# CntrlBoardV2_0.net
KiCad netlist of a schematic drawn in EAGLE
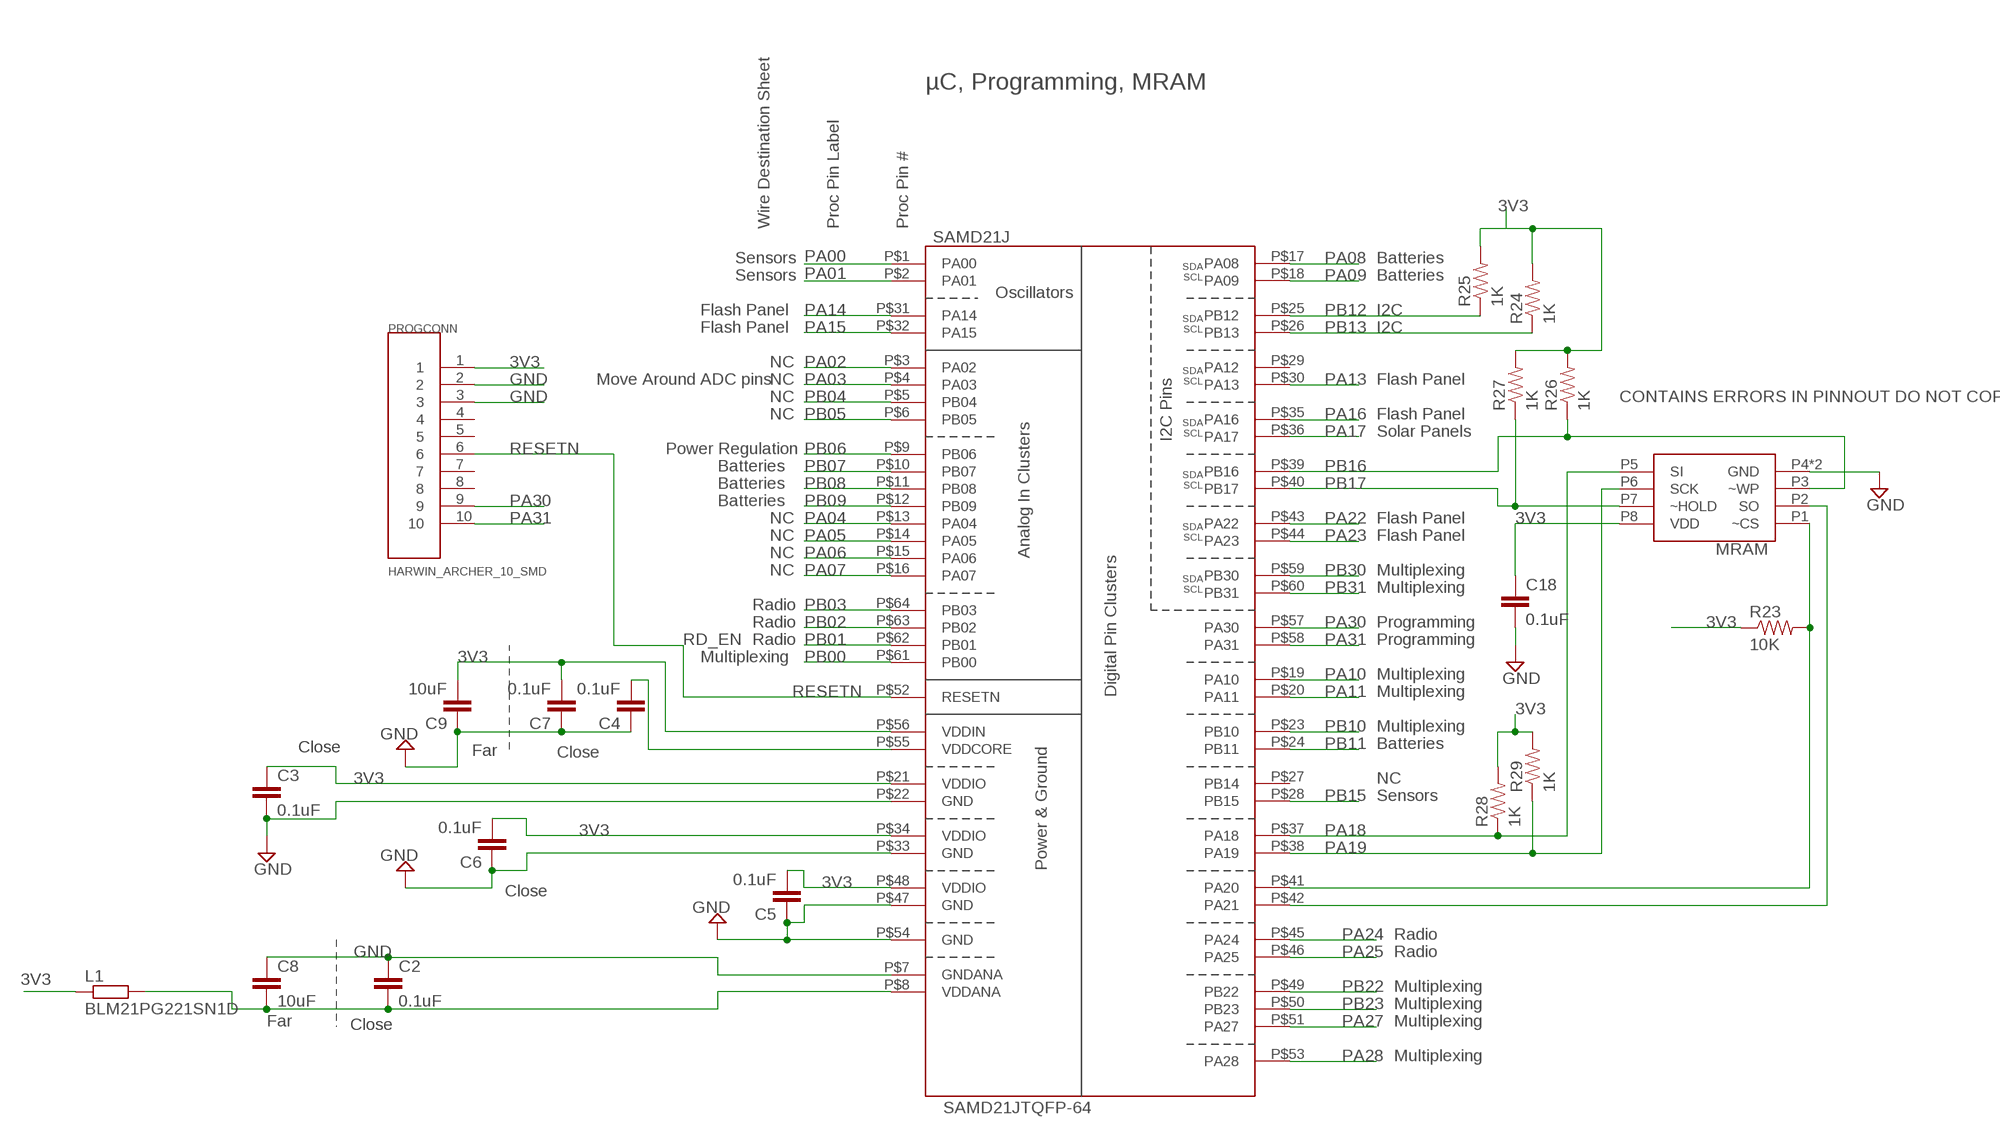
[diagram p0: schematic, sheet 1]
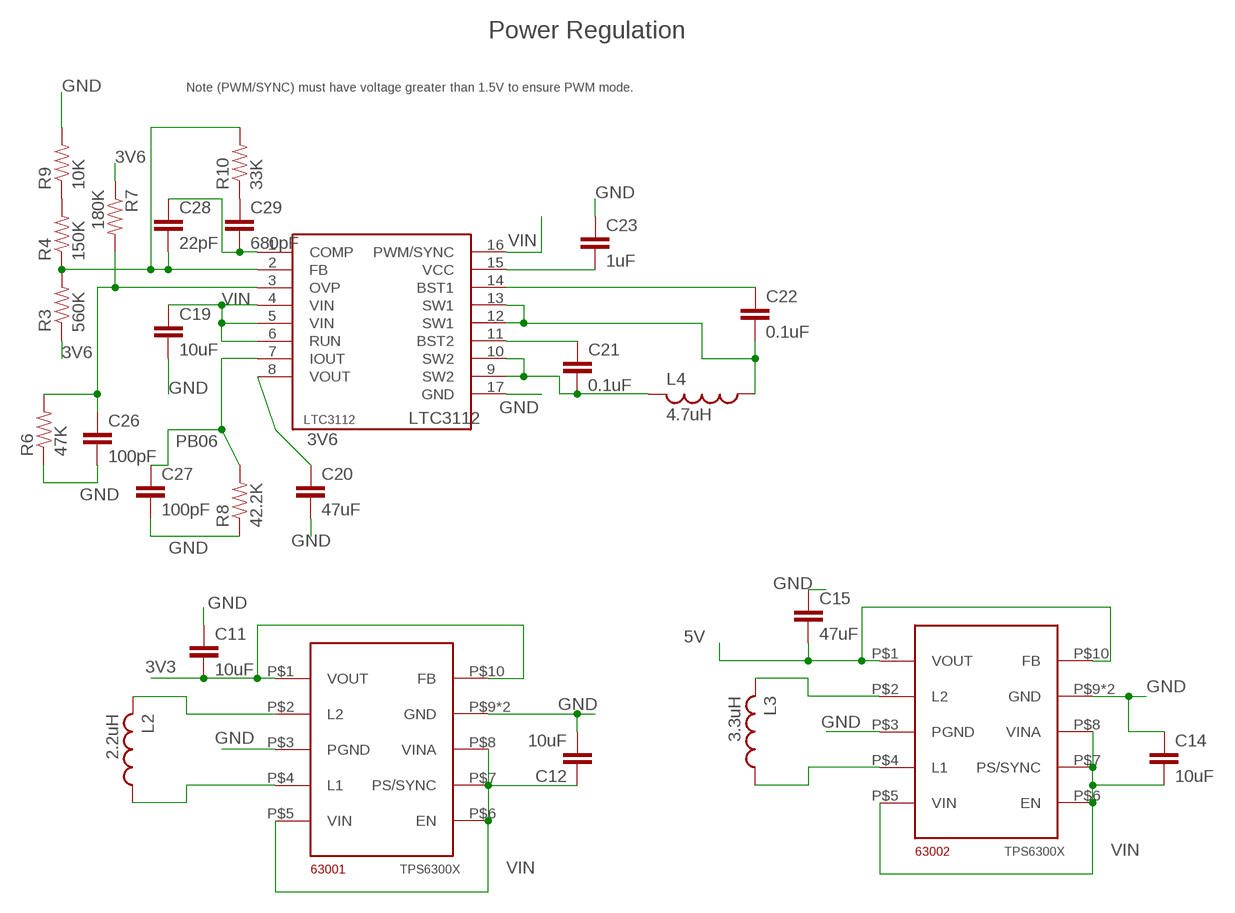
[diagram p1: schematic, sheet 2]
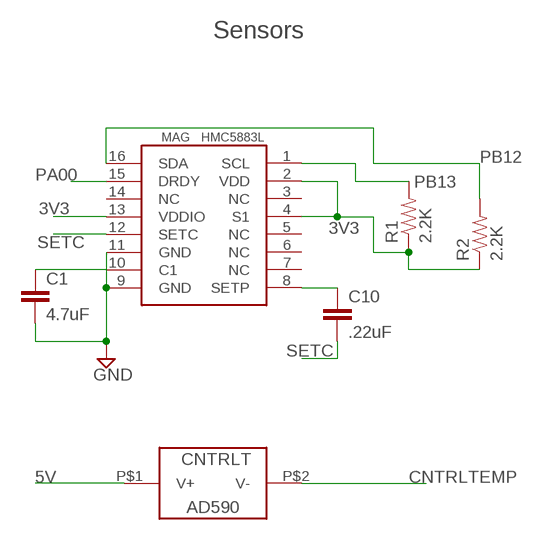
[diagram p2: schematic, sheet 3]
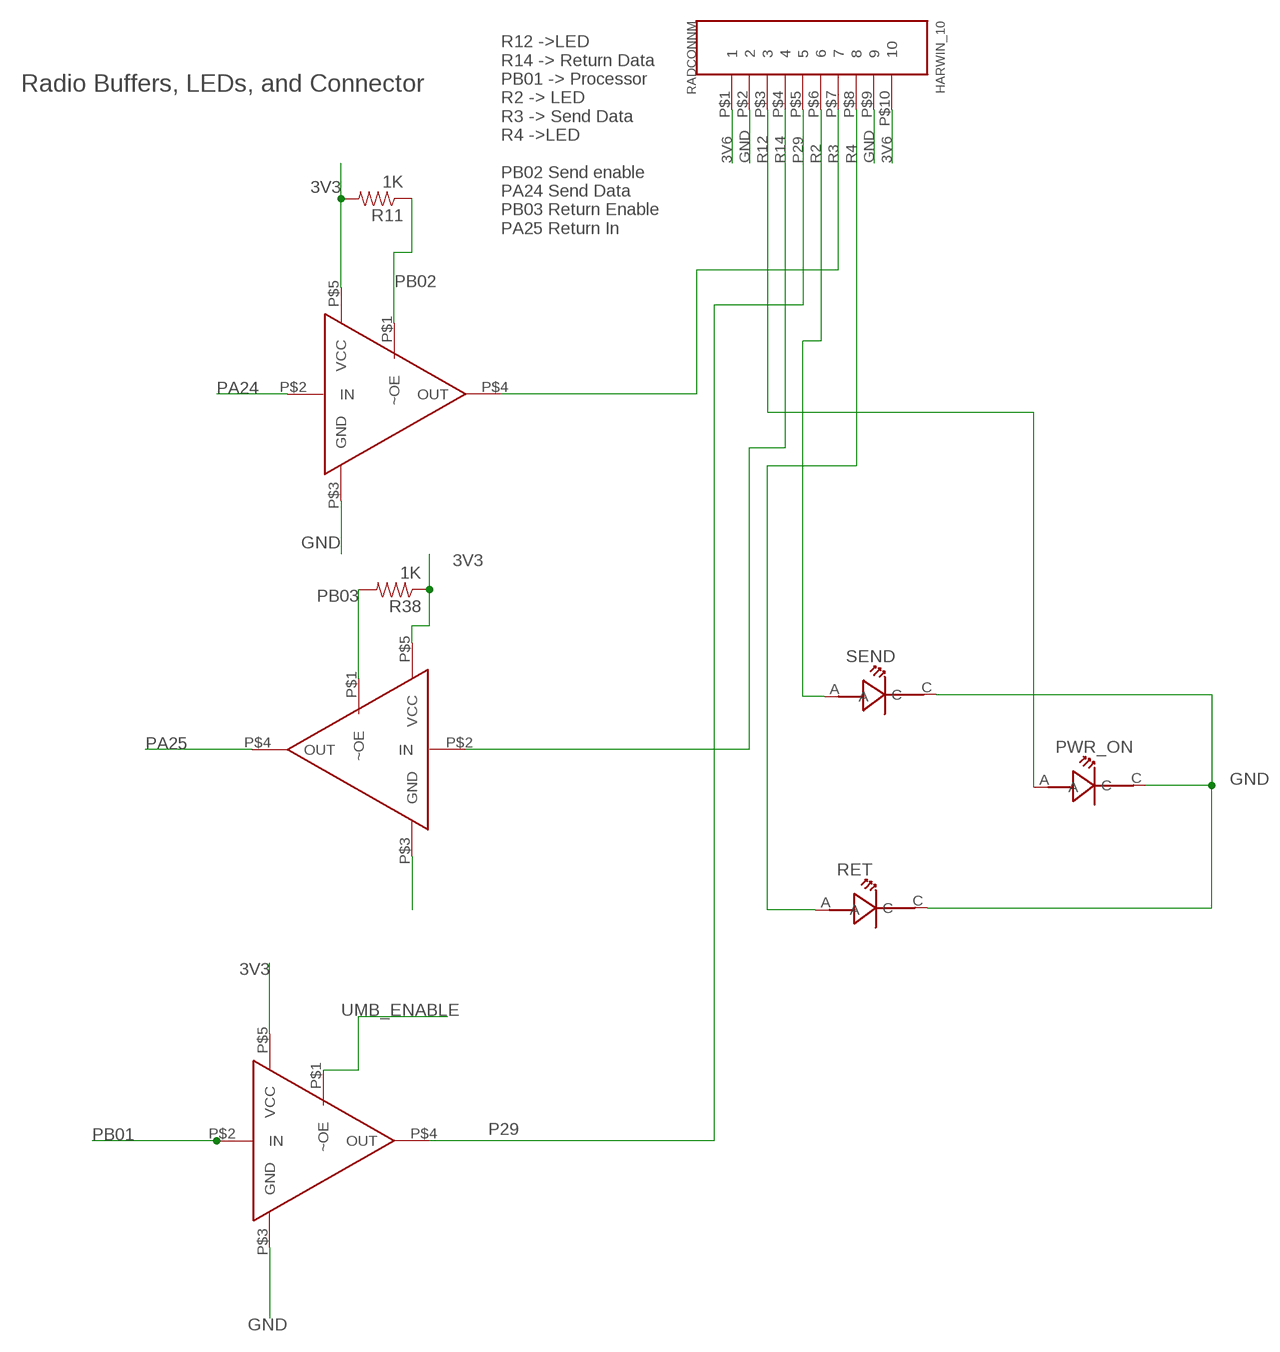
[diagram p3: schematic, sheet 4]
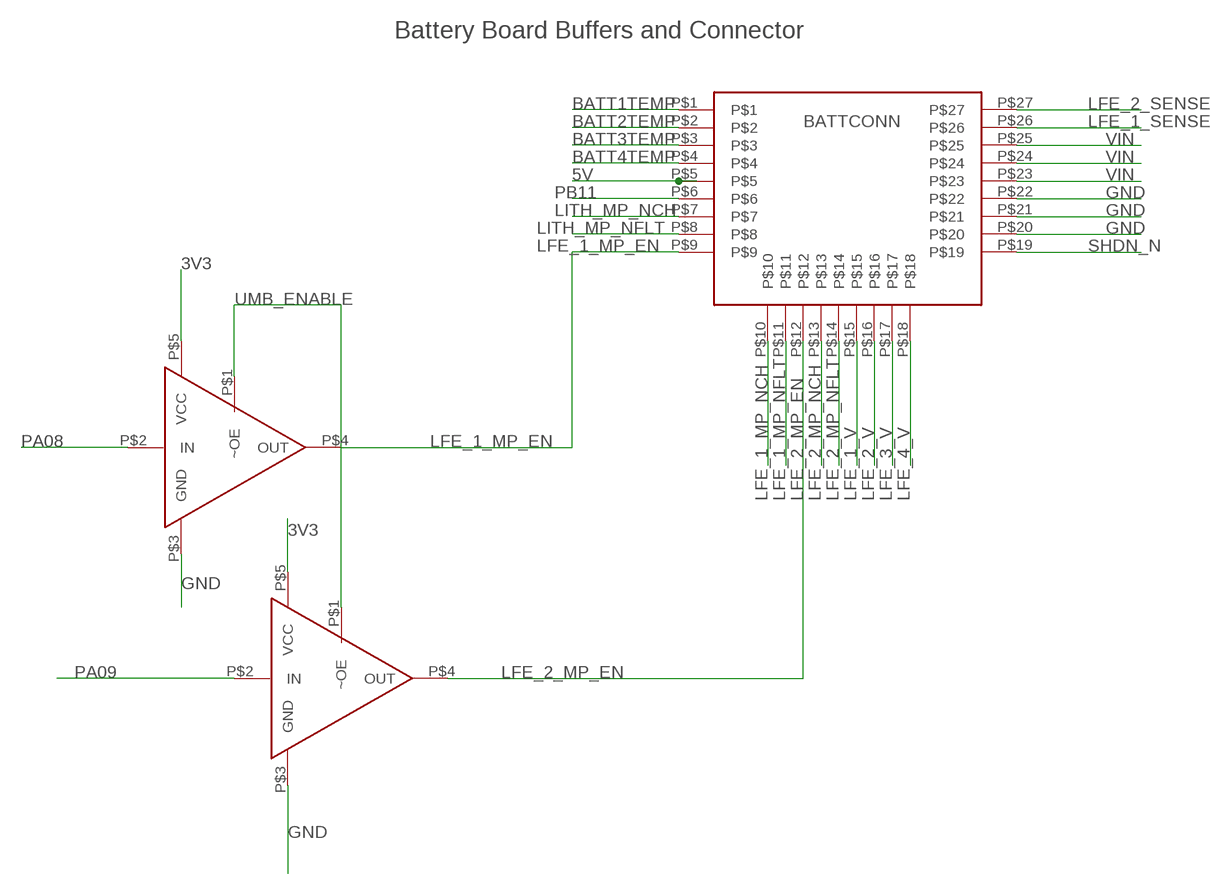
[diagram p4: schematic, sheet 5]
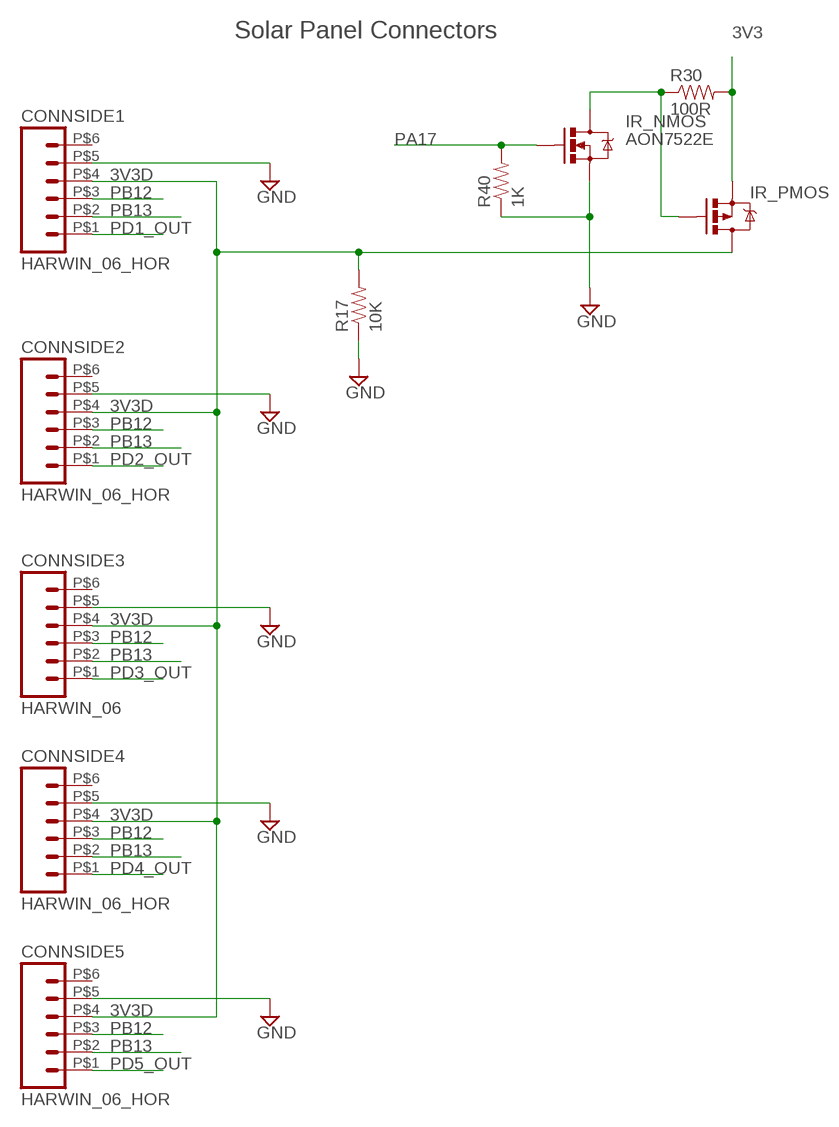
[diagram p5: schematic, sheet 6]
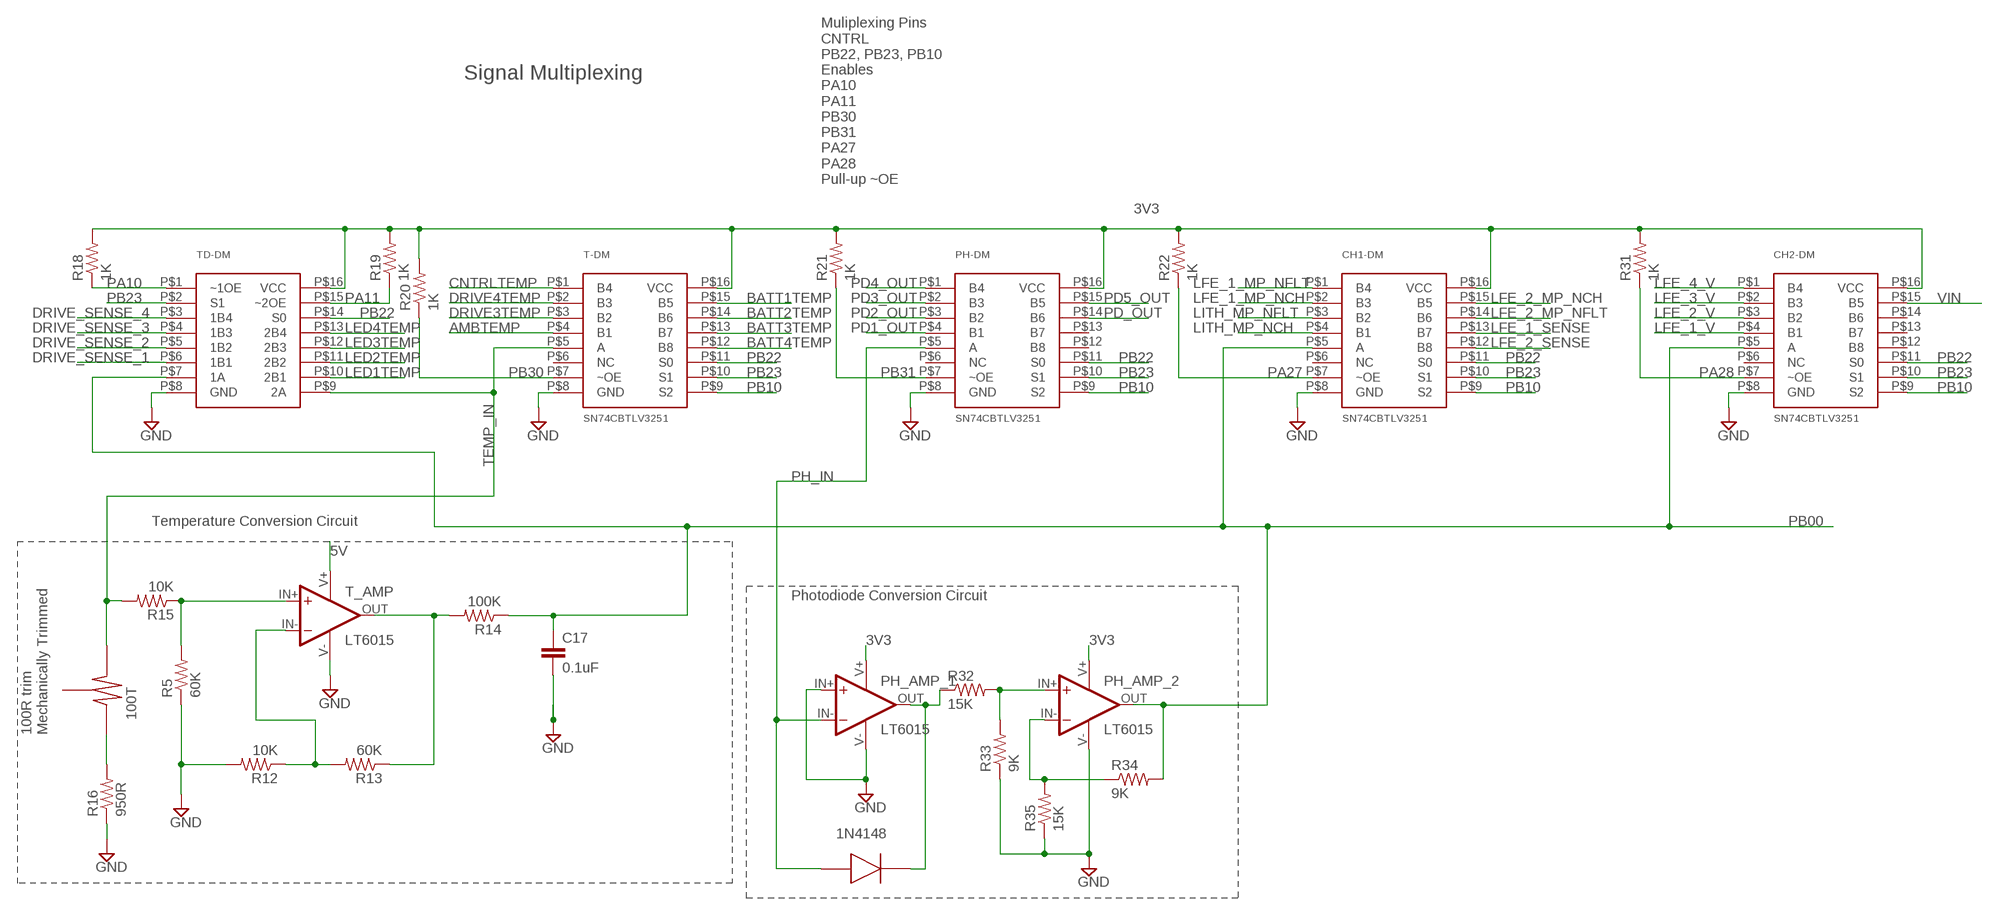
[diagram p6: schematic, sheet 7]
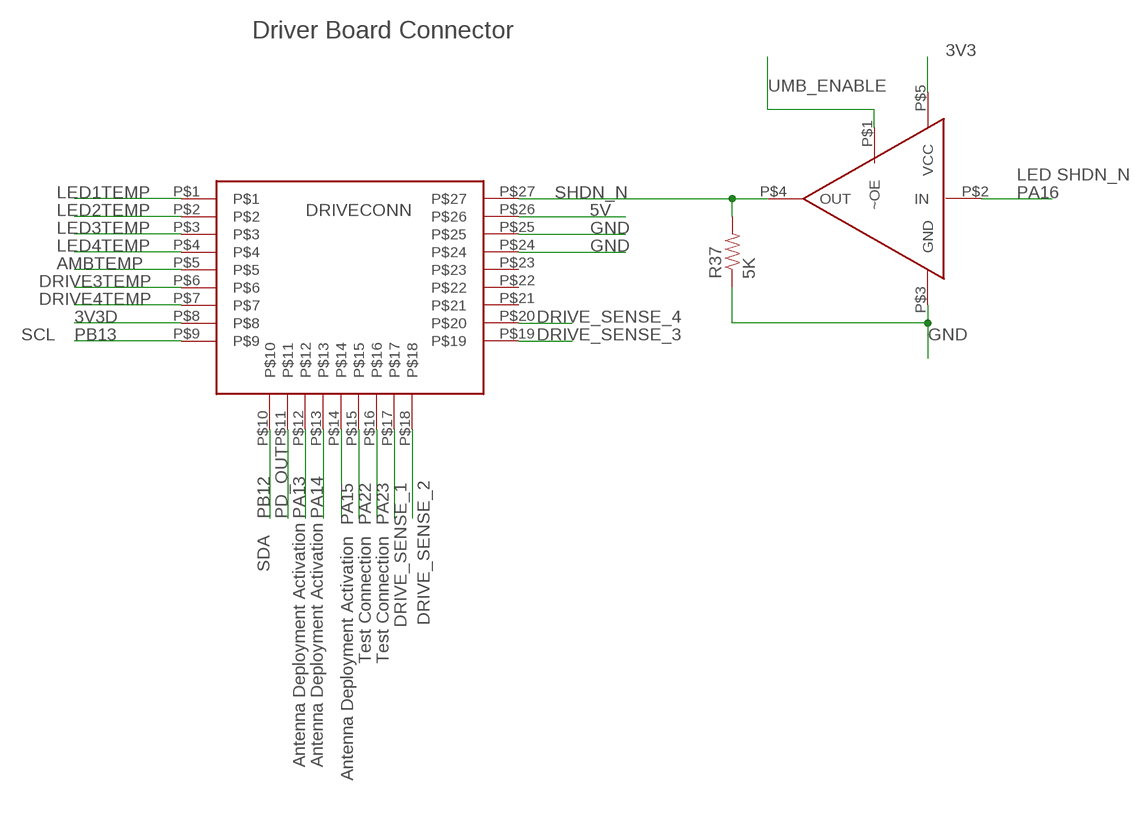
[diagram p7: schematic, sheet 8]
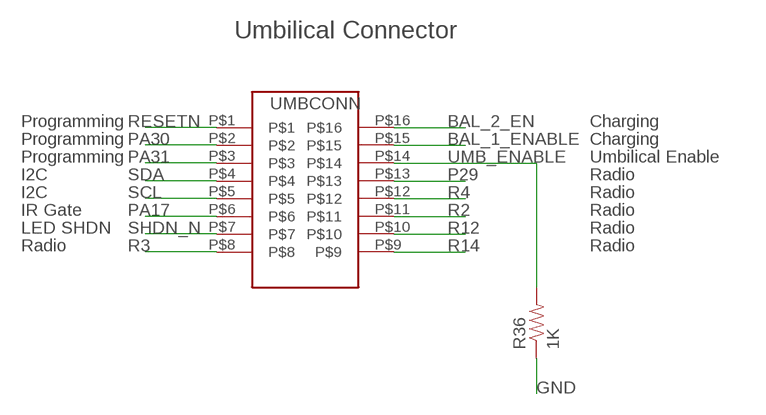
[diagram p8: schematic, sheet 9]

(export (version "E")
  (design (tool "Eeschema 10.0.6"))
  (components
    (comp (ref "DRIVECONN")
      (value "HARWIN_27_HOR")
      (footprint "eagle-import:HARWIN_DATAMATE_27_HOR")
      (libsource (lib "eagle-import") (part "HARWIN_27_HOR"))
    )
    (comp (ref "LED_EN_BUF")
      (value "SN74LVC1G125")
      (footprint "eagle-import:SC70")
      (libsource (lib "eagle-import") (part "SN74LVC1G125"))
    )
    (comp (ref "R37")
      (value "5K")
      (footprint "eagle-import:0805")
      (libsource (lib "eagle-import") (part "RESISTOR"))
    )
    (comp (ref "R36")
      (value "1K")
      (footprint "eagle-import:0805")
      (libsource (lib "eagle-import") (part "RESISTOR"))
    )
    (comp (ref "UMBCONN")
      (value "HARWIN_16")
      (footprint "eagle-import:HARWIN_DATAMATE_16")
      (libsource (lib "eagle-import") (part "HARWIN_16"))
    )
    (comp (ref "BAL_1_BUF")
      (value "SN74LVC1G125")
      (footprint "eagle-import:SC70")
      (libsource (lib "eagle-import") (part "SN74LVC1G125"))
    )
    (comp (ref "BAL_2_BUF")
      (value "SN74LVC1G125")
      (footprint "eagle-import:SC70")
      (libsource (lib "eagle-import") (part "SN74LVC1G125"))
    )
    (comp (ref "BATTCONN")
      (value "HARWIN_27")
      (footprint "eagle-import:HARWIN_DATAMATE_27")
      (libsource (lib "eagle-import") (part "HARWIN_27"))
    )
    (comp (ref "1N4148")
      (value "1N4148WS")
      (footprint "eagle-import:SOD-323F")
      (libsource (lib "eagle-import") (part "1N4148WS"))
    )
    (comp (ref "100T")
      (value "TRIMPOT-TC33")
      (footprint "eagle-import:TC33X-2")
      (libsource (lib "eagle-import") (part "TRIMPOT-TC33"))
    )
    (comp (ref "C17")
      (value "0.1uF")
      (footprint "eagle-import:0805")
      (libsource (lib "eagle-import") (part "CAP0805"))
    )
    (comp (ref "CH1-DM")
      (value "SN74CBTLV3251")
      (footprint "eagle-import:TSSOP-16")
      (libsource (lib "eagle-import") (part "SN74CBTLV3251"))
    )
    (comp (ref "CH2-DM")
      (value "SN74CBTLV3251")
      (footprint "eagle-import:TSSOP-16")
      (libsource (lib "eagle-import") (part "SN74CBTLV3251"))
    )
    (comp (ref "PH-DM")
      (value "SN74CBTLV3251")
      (footprint "eagle-import:TSSOP-16")
      (libsource (lib "eagle-import") (part "SN74CBTLV3251"))
    )
    (comp (ref "PH_AMP_1")
      (value "LT6015")
      (footprint "eagle-import:SOT23-5")
      (libsource (lib "eagle-import") (part "LT6015"))
    )
    (comp (ref "PH_AMP_2")
      (value "LT6015")
      (footprint "eagle-import:SOT23-5")
      (libsource (lib "eagle-import") (part "LT6015"))
    )
    (comp (ref "R5")
      (value "60K")
      (footprint "eagle-import:0805")
      (libsource (lib "eagle-import") (part "RESISTOR"))
    )
    (comp (ref "R12")
      (value "10K")
      (footprint "eagle-import:0805")
      (libsource (lib "eagle-import") (part "RESISTOR"))
    )
    (comp (ref "R13")
      (value "60K")
      (footprint "eagle-import:0805")
      (libsource (lib "eagle-import") (part "RESISTOR"))
    )
    (comp (ref "R14")
      (value "100K")
      (footprint "eagle-import:0805")
      (libsource (lib "eagle-import") (part "RESISTOR"))
    )
    (comp (ref "R15")
      (value "10K")
      (footprint "eagle-import:0805")
      (libsource (lib "eagle-import") (part "RESISTOR"))
    )
    (comp (ref "R16")
      (value "950R")
      (footprint "eagle-import:0805")
      (libsource (lib "eagle-import") (part "RESISTOR"))
    )
    (comp (ref "R18")
      (value "1K")
      (footprint "eagle-import:0805")
      (libsource (lib "eagle-import") (part "RESISTOR"))
    )
    (comp (ref "R19")
      (value "1K")
      (footprint "eagle-import:0805")
      (libsource (lib "eagle-import") (part "RESISTOR"))
    )
    (comp (ref "R20")
      (value "1K")
      (footprint "eagle-import:0805")
      (libsource (lib "eagle-import") (part "RESISTOR"))
    )
    (comp (ref "R21")
      (value "1K")
      (footprint "eagle-import:0805")
      (libsource (lib "eagle-import") (part "RESISTOR"))
    )
    (comp (ref "R22")
      (value "1K")
      (footprint "eagle-import:0805")
      (libsource (lib "eagle-import") (part "RESISTOR"))
    )
    (comp (ref "R31")
      (value "1K")
      (footprint "eagle-import:0805")
      (libsource (lib "eagle-import") (part "RESISTOR"))
    )
    (comp (ref "R32")
      (value "15K")
      (footprint "eagle-import:0805")
      (libsource (lib "eagle-import") (part "RESISTOR"))
    )
    (comp (ref "R33")
      (value "9K")
      (footprint "eagle-import:0805")
      (libsource (lib "eagle-import") (part "RESISTOR"))
    )
    (comp (ref "R34")
      (value "9K")
      (footprint "eagle-import:0805")
      (libsource (lib "eagle-import") (part "RESISTOR"))
    )
    (comp (ref "R35")
      (value "15K")
      (footprint "eagle-import:0805")
      (libsource (lib "eagle-import") (part "RESISTOR"))
    )
    (comp (ref "T-DM")
      (value "SN74CBTLV3251")
      (footprint "eagle-import:TSSOP-16")
      (libsource (lib "eagle-import") (part "SN74CBTLV3251"))
    )
    (comp (ref "TD-DM")
      (value "SN74CBTLV3253")
      (footprint "eagle-import:TSSOP-16")
      (libsource (lib "eagle-import") (part "SN74CBTLV3253"))
    )
    (comp (ref "T_AMP")
      (value "LT6015")
      (footprint "eagle-import:SOT23-5")
      (libsource (lib "eagle-import") (part "LT6015"))
    )
    (comp (ref "63001")
      (value "TPS6300X")
      (footprint "eagle-import:QFN10_POWERPAD")
      (libsource (lib "eagle-import") (part "TPS6300X"))
    )
    (comp (ref "63002")
      (value "TPS6300X")
      (footprint "eagle-import:QFN10_POWERPAD")
      (libsource (lib "eagle-import") (part "TPS6300X"))
    )
    (comp (ref "C11")
      (value "10uF")
      (footprint "eagle-import:0603-CAP")
      (libsource (lib "eagle-import") (part "CAP0603-CAP"))
    )
    (comp (ref "C12")
      (value "10uF")
      (footprint "eagle-import:0603-CAP")
      (libsource (lib "eagle-import") (part "CAP0603-CAP"))
    )
    (comp (ref "C14")
      (value "10uF")
      (footprint "eagle-import:0603-CAP")
      (fields (field (name "MPN") "C1608X5R1A225K080AC"))
      (libsource (lib "eagle-import") (part "CAP0603-CAP"))
    )
    (comp (ref "C15")
      (value "47uF")
      (footprint "eagle-import:0603-CAP")
      (fields (field (name "MPN") "EMK107B7474KA-T"))
      (libsource (lib "eagle-import") (part "CAP0603-CAP"))
    )
    (comp (ref "C19")
      (value "10uF")
      (footprint "eagle-import:0603-CAP")
      (libsource (lib "eagle-import") (part "CAP0603-CAP"))
    )
    (comp (ref "C20")
      (value "47uF")
      (footprint "eagle-import:0805")
      (fields (field (name "MPN") "EMK107B7474KA-T"))
      (libsource (lib "eagle-import") (part "CAP0805"))
    )
    (comp (ref "C21")
      (value "0.1uF")
      (footprint "eagle-import:0603-CAP")
      (fields (field (name "MPN") "0603YC104JAT2A"))
      (libsource (lib "eagle-import") (part "CAP0603-CAP"))
    )
    (comp (ref "C22")
      (value "0.1uF")
      (footprint "eagle-import:0603-CAP")
      (fields (field (name "MPN") "0603YC104JAT2A"))
      (libsource (lib "eagle-import") (part "CAP0603-CAP"))
    )
    (comp (ref "C23")
      (value "1uF")
      (footprint "eagle-import:0603-CAP")
      (libsource (lib "eagle-import") (part "CAP0603-CAP"))
    )
    (comp (ref "C26")
      (value "100pF")
      (footprint "eagle-import:0805")
      (fields (field (name "MF") "AVX CORPORATION") (field (name "MPN") "08051A101J4T4A"))
      (libsource (lib "eagle-import") (part "CAP0805"))
    )
    (comp (ref "C27")
      (value "100pF")
      (footprint "eagle-import:0805")
      (fields (field (name "MF") "AVX CORPORATION") (field (name "MPN") "08051A101J4T4A"))
      (libsource (lib "eagle-import") (part "CAP0805"))
    )
    (comp (ref "C28")
      (value "22pF")
      (footprint "eagle-import:0805")
      (fields (field (name "MF") "AVX CORPORATION") (field (name "MPN") "08051A220JAT2A"))
      (libsource (lib "eagle-import") (part "CAP0805"))
    )
    (comp (ref "C29")
      (value "680pF")
      (footprint "eagle-import:0805")
      (fields (field (name "MPN") "08055C681KAT2A"))
      (libsource (lib "eagle-import") (part "CAP0805"))
    )
    (comp (ref "L2")
      (value "2.2uH")
      (footprint "eagle-import:L3225M")
      (libsource (lib "eagle-import") (part "L-USL3225M"))
    )
    (comp (ref "L3")
      (value "3.3uH")
      (footprint "eagle-import:L3225M")
      (fields (field (name "MPN") "JMK212BJ335KG-T"))
      (libsource (lib "eagle-import") (part "L-USL3225M"))
    )
    (comp (ref "L4")
      (value "4.7uH")
      (footprint "eagle-import:L3225M")
      (libsource (lib "eagle-import") (part "L-USL3225M"))
    )
    (comp (ref "LTC3112")
      (value "LTC3112")
      (footprint "eagle-import:DHD16")
      (fields (field (name "MPN") "LTC3112EFE#PBF"))
      (libsource (lib "eagle-import") (part "LTC3112"))
    )
    (comp (ref "R3")
      (value "560K")
      (footprint "eagle-import:0805")
      (fields (field (name "MPN") "MC01W08051560K"))
      (libsource (lib "eagle-import") (part "RESISTOR"))
    )
    (comp (ref "R4")
      (value "150K")
      (footprint "eagle-import:0805")
      (libsource (lib "eagle-import") (part "RESISTOR"))
    )
    (comp (ref "R6")
      (value "47K")
      (footprint "eagle-import:0805")
      (libsource (lib "eagle-import") (part "RESISTOR"))
    )
    (comp (ref "R7")
      (value "180K")
      (footprint "eagle-import:0805")
      (fields (field (name "MPN") "ERJ-6GEYJ184V"))
      (libsource (lib "eagle-import") (part "RESISTOR"))
    )
    (comp (ref "R8")
      (value "42.2K")
      (footprint "eagle-import:0805")
      (libsource (lib "eagle-import") (part "RESISTOR"))
    )
    (comp (ref "R9")
      (value "10K")
      (footprint "eagle-import:0805")
      (libsource (lib "eagle-import") (part "RESISTOR"))
    )
    (comp (ref "R10")
      (value "33K")
      (footprint "eagle-import:0805")
      (libsource (lib "eagle-import") (part "RESISTOR"))
    )
    (comp (ref "C2")
      (value "0.1uF")
      (footprint "eagle-import:0805")
      (fields (field (name "MPN") "0603YC104JAT2A"))
      (libsource (lib "eagle-import") (part "CAP0805"))
    )
    (comp (ref "C3")
      (value "0.1uF")
      (footprint "eagle-import:0805")
      (fields (field (name "MPN") "0603YC104JAT2A"))
      (libsource (lib "eagle-import") (part "CAP0805"))
    )
    (comp (ref "C4")
      (value "0.1uF")
      (footprint "eagle-import:0805")
      (fields (field (name "MPN") "0603YC104JAT2A"))
      (libsource (lib "eagle-import") (part "CAP0805"))
    )
    (comp (ref "C5")
      (value "0.1uF")
      (footprint "eagle-import:0805")
      (fields (field (name "MPN") "0603YC104JAT2A"))
      (libsource (lib "eagle-import") (part "CAP0805"))
    )
    (comp (ref "C6")
      (value "0.1uF")
      (footprint "eagle-import:0805")
      (fields (field (name "MPN") "0603YC104JAT2A"))
      (libsource (lib "eagle-import") (part "CAP0805"))
    )
    (comp (ref "C7")
      (value "0.1uF")
      (footprint "eagle-import:0805")
      (fields (field (name "MPN") "0603YC104JAT2A"))
      (libsource (lib "eagle-import") (part "CAP0805"))
    )
    (comp (ref "C8")
      (value "10uF")
      (footprint "eagle-import:0805")
      (fields (field (name "MF") "AVX CORPORATION") (field (name "MPN") "08056D106KAT2A"))
      (libsource (lib "eagle-import") (part "CAP0805"))
    )
    (comp (ref "C9")
      (value "10uF")
      (footprint "eagle-import:0805")
      (fields (field (name "MF") "AVX CORPORATION") (field (name "MPN") "08056D106KAT2A"))
      (libsource (lib "eagle-import") (part "CAP0805"))
    )
    (comp (ref "C18")
      (value "0.1uF")
      (footprint "eagle-import:0805")
      (fields (field (name "MPN") "0603YC104JAT2A"))
      (libsource (lib "eagle-import") (part "CAP0805"))
    )
    (comp (ref "L1")
      (value "BLM21PG221SN1D")
      (footprint "eagle-import:R0805")
      (libsource (lib "eagle-import") (part "R-EU_R0805"))
    )
    (comp (ref "MRAM")
      (value "MR25H10CDC")
      (footprint "eagle-import:8PXMO-229")
      (libsource (lib "eagle-import") (part "MR25H10CDC"))
    )
    (comp (ref "PROGCONN")
      (value "HARWIN_ARCHER_10_SMD")
      (footprint "eagle-import:HARWIN_ARCHER_10_SMD")
      (libsource (lib "eagle-import") (part "HARWIN_ARCHER_10_SMD"))
    )
    (comp (ref "R23")
      (value "10K")
      (footprint "eagle-import:0805")
      (libsource (lib "eagle-import") (part "RESISTOR"))
    )
    (comp (ref "R24")
      (value "1K")
      (footprint "eagle-import:0805")
      (libsource (lib "eagle-import") (part "RESISTOR"))
    )
    (comp (ref "R25")
      (value "1K")
      (footprint "eagle-import:0805")
      (libsource (lib "eagle-import") (part "RESISTOR"))
    )
    (comp (ref "R26")
      (value "1K")
      (footprint "eagle-import:0805")
      (libsource (lib "eagle-import") (part "RESISTOR"))
    )
    (comp (ref "R27")
      (value "1K")
      (footprint "eagle-import:0805")
      (libsource (lib "eagle-import") (part "RESISTOR"))
    )
    (comp (ref "R28")
      (value "1K")
      (footprint "eagle-import:0805")
      (libsource (lib "eagle-import") (part "RESISTOR"))
    )
    (comp (ref "R29")
      (value "1K")
      (footprint "eagle-import:0805")
      (libsource (lib "eagle-import") (part "RESISTOR"))
    )
    (comp (ref "SAMD21J")
      (value "SAMD21JTQFP-64")
      (footprint "eagle-import:TQFP-64")
      (libsource (lib "eagle-import") (part "SAMD21JTQFP-64"))
    )
    (comp (ref "C1")
      (value "4.7uF")
      (footprint "eagle-import:0805")
      (fields (field (name "MF") "AVX CORPORATION") (field (name "MPN") "08056D475KAT2A"))
      (libsource (lib "eagle-import") (part "CAP0805"))
    )
    (comp (ref "C10")
      (value ".22uF")
      (footprint "eagle-import:0805")
      (fields (field (name "MF") "AVX CORPORATION") (field (name "MPN") "08053C224KAT2A"))
      (libsource (lib "eagle-import") (part "CAP0805"))
    )
    (comp (ref "CNTRLT")
      (value "AD590-TH")
      (footprint "eagle-import:AD590TH")
      (libsource (lib "eagle-import") (part "AD590-TH"))
    )
    (comp (ref "MAG")
      (value "HMC5883L")
      (footprint "eagle-import:HMC5883L")
      (fields (field (name "MPN") "HMC5883L-TR"))
      (libsource (lib "eagle-import") (part "HMC5883L"))
    )
    (comp (ref "R1")
      (value "2.2K")
      (footprint "eagle-import:0805")
      (fields (field (name "MPN") "SR1-0805-222"))
      (libsource (lib "eagle-import") (part "RESISTOR"))
    )
    (comp (ref "R2")
      (value "2.2K")
      (footprint "eagle-import:0805")
      (fields (field (name "MPN") "SR1-0805-222"))
      (libsource (lib "eagle-import") (part "RESISTOR"))
    )
    (comp (ref "PWR_ON")
      (value "LT-T673-Q1R2-25-Z")
      (footprint "eagle-import:PLCC-2")
      (libsource (lib "eagle-import") (part "LT-T673-Q1R2-25-Z"))
    )
    (comp (ref "R11")
      (value "1K")
      (footprint "eagle-import:0805")
      (libsource (lib "eagle-import") (part "RESISTOR"))
    )
    (comp (ref "R38")
      (value "1K")
      (footprint "eagle-import:0805")
      (libsource (lib "eagle-import") (part "RESISTOR"))
    )
    (comp (ref "RADCONNM")
      (value "HARWIN_10")
      (footprint "eagle-import:HARWIN_DATAMATE_10")
      (libsource (lib "eagle-import") (part "HARWIN_10"))
    )
    (comp (ref "RAD_SHDN_BUF")
      (value "SN74LVC1G125")
      (footprint "eagle-import:SC70")
      (libsource (lib "eagle-import") (part "SN74LVC1G125"))
    )
    (comp (ref "RET")
      (value "LT-T673-Q1R2-25-Z")
      (footprint "eagle-import:PLCC-2")
      (libsource (lib "eagle-import") (part "LT-T673-Q1R2-25-Z"))
    )
    (comp (ref "RX_BUF")
      (value "SN74LVC1G125")
      (footprint "eagle-import:SC70")
      (libsource (lib "eagle-import") (part "SN74LVC1G125"))
    )
    (comp (ref "SEND")
      (value "LT-T673-Q1R2-25-Z")
      (footprint "eagle-import:PLCC-2")
      (libsource (lib "eagle-import") (part "LT-T673-Q1R2-25-Z"))
    )
    (comp (ref "TX_BUF")
      (value "SN74LVC1G125")
      (footprint "eagle-import:SC70")
      (libsource (lib "eagle-import") (part "SN74LVC1G125"))
    )
    (comp (ref "CONNSIDE1")
      (value "HARWIN_06_HOR")
      (footprint "eagle-import:HARWIN_DATAMATE_6_HOR")
      (libsource (lib "eagle-import") (part "HARWIN_06_HOR"))
    )
    (comp (ref "CONNSIDE2")
      (value "HARWIN_06_HOR")
      (footprint "eagle-import:HARWIN_DATAMATE_6_HOR")
      (libsource (lib "eagle-import") (part "HARWIN_06_HOR"))
    )
    (comp (ref "CONNSIDE3")
      (value "HARWIN_06")
      (footprint "eagle-import:HARWIN_DATAMATE_6")
      (libsource (lib "eagle-import") (part "HARWIN_06"))
    )
    (comp (ref "CONNSIDE4")
      (value "HARWIN_06_HOR")
      (footprint "eagle-import:HARWIN_DATAMATE_6_HOR")
      (libsource (lib "eagle-import") (part "HARWIN_06_HOR"))
    )
    (comp (ref "CONNSIDE5")
      (value "HARWIN_06_HOR")
      (footprint "eagle-import:HARWIN_DATAMATE_6_HOR")
      (libsource (lib "eagle-import") (part "HARWIN_06_HOR"))
    )
    (comp (ref "IR_NMOS")
      (value "AON7522E")
      (footprint "eagle-import:DFN3")
      (libsource (lib "eagle-import") (part "AON7522E"))
    )
    (comp (ref "IR_PMOS")
      (value "POWERPMOS")
      (footprint "eagle-import:SO08")
      (libsource (lib "eagle-import") (part "POWERPMOS"))
    )
    (comp (ref "R17")
      (value "10K")
      (footprint "eagle-import:0805")
      (libsource (lib "eagle-import") (part "RESISTOR"))
    )
    (comp (ref "R30")
      (value "100R")
      (footprint "eagle-import:0805")
      (libsource (lib "eagle-import") (part "RESISTOR"))
    )
    (comp (ref "R40")
      (value "1K")
      (footprint "eagle-import:0805")
      (libsource (lib "eagle-import") (part "RESISTOR"))
    )
  )
  (nets
    (net (code "1") (name "3V3") (class "Default")
      (node (ref "63001") (pin "P$1") (pinfunction "VOUT_P$1") (pintype "output"))
      (node (ref "63001") (pin "P$10") (pinfunction "FB_P$10") (pintype "input"))
      (node (ref "BAL_1_BUF") (pin "P$5") (pinfunction "VCC_P$5") (pintype "bidirectional"))
      (node (ref "BAL_2_BUF") (pin "P$5") (pinfunction "VCC_P$5") (pintype "bidirectional"))
      (node (ref "C11") (pin "2") (pinfunction "2_2") (pintype "passive"))
      (node (ref "C18") (pin "1") (pinfunction "1_1") (pintype "passive"))
      (node (ref "C3") (pin "1") (pinfunction "1_1") (pintype "passive"))
      (node (ref "C5") (pin "2") (pinfunction "2_2") (pintype "passive"))
      (node (ref "C6") (pin "2") (pinfunction "2_2") (pintype "passive"))
      (node (ref "C7") (pin "2") (pinfunction "2_2") (pintype "passive"))
      (node (ref "C9") (pin "2") (pinfunction "2_2") (pintype "passive"))
      (node (ref "CH1-DM") (pin "P$16") (pinfunction "VCC_P$16") (pintype "bidirectional"))
      (node (ref "CH2-DM") (pin "P$16") (pinfunction "VCC_P$16") (pintype "bidirectional"))
      (node (ref "IR_PMOS") (pin "1") (pinfunction "S_1") (pintype "passive"))
      (node (ref "IR_PMOS") (pin "2") (pinfunction "S_2") (pintype "passive"))
      (node (ref "IR_PMOS") (pin "3") (pinfunction "S_3") (pintype "passive"))
      (node (ref "L1") (pin "1") (pinfunction "1_1") (pintype "passive"))
      (node (ref "LED_EN_BUF") (pin "P$5") (pinfunction "VCC_P$5") (pintype "bidirectional"))
      (node (ref "MAG") (pin "13") (pinfunction "VDDIO_13") (pintype "bidirectional"))
      (node (ref "MAG") (pin "2") (pinfunction "VDD_2") (pintype "bidirectional"))
      (node (ref "MAG") (pin "4") (pinfunction "S1_4") (pintype "bidirectional"))
      (node (ref "MRAM") (pin "P8") (pinfunction "VDD_P8") (pintype "bidirectional"))
      (node (ref "PH-DM") (pin "P$16") (pinfunction "VCC_P$16") (pintype "bidirectional"))
      (node (ref "PH_AMP_1") (pin "V+") (pinfunction "V+_V+") (pintype "power_in"))
      (node (ref "PH_AMP_2") (pin "V+") (pinfunction "V+_V+") (pintype "power_in"))
      (node (ref "PROGCONN") (pin "1") (pinfunction "1_1") (pintype "bidirectional"))
      (node (ref "R1") (pin "1") (pinfunction "1_1") (pintype "passive"))
      (node (ref "R11") (pin "2") (pinfunction "2_2") (pintype "passive"))
      (node (ref "R18") (pin "2") (pinfunction "2_2") (pintype "passive"))
      (node (ref "R19") (pin "2") (pinfunction "2_2") (pintype "passive"))
      (node (ref "R2") (pin "1") (pinfunction "1_1") (pintype "passive"))
      (node (ref "R20") (pin "2") (pinfunction "2_2") (pintype "passive"))
      (node (ref "R21") (pin "2") (pinfunction "2_2") (pintype "passive"))
      (node (ref "R22") (pin "2") (pinfunction "2_2") (pintype "passive"))
      (node (ref "R23") (pin "1") (pinfunction "1_1") (pintype "passive"))
      (node (ref "R24") (pin "2") (pinfunction "2_2") (pintype "passive"))
      (node (ref "R25") (pin "2") (pinfunction "2_2") (pintype "passive"))
      (node (ref "R26") (pin "2") (pinfunction "2_2") (pintype "passive"))
      (node (ref "R27") (pin "2") (pinfunction "2_2") (pintype "passive"))
      (node (ref "R28") (pin "2") (pinfunction "2_2") (pintype "passive"))
      (node (ref "R29") (pin "2") (pinfunction "2_2") (pintype "passive"))
      (node (ref "R30") (pin "2") (pinfunction "2_2") (pintype "passive"))
      (node (ref "R31") (pin "2") (pinfunction "2_2") (pintype "passive"))
      (node (ref "R38") (pin "1") (pinfunction "1_1") (pintype "passive"))
      (node (ref "RAD_SHDN_BUF") (pin "P$5") (pinfunction "VCC_P$5") (pintype "bidirectional"))
      (node (ref "RX_BUF") (pin "P$5") (pinfunction "VCC_P$5") (pintype "bidirectional"))
      (node (ref "SAMD21J") (pin "P$21") (pinfunction "VDDIO_P$21") (pintype "power_in"))
      (node (ref "SAMD21J") (pin "P$34") (pinfunction "VDDIO_P$34") (pintype "power_in"))
      (node (ref "SAMD21J") (pin "P$48") (pinfunction "VDDIO_P$48") (pintype "power_in"))
      (node (ref "SAMD21J") (pin "P$56") (pinfunction "VDDIN_P$56") (pintype "power_in"))
      (node (ref "T-DM") (pin "P$16") (pinfunction "VCC_P$16") (pintype "bidirectional"))
      (node (ref "TD-DM") (pin "P$16") (pinfunction "VCC_P$16") (pintype "bidirectional"))
      (node (ref "TX_BUF") (pin "P$5") (pinfunction "VCC_P$5") (pintype "bidirectional"))
    )
    (net (code "2") (name "3V3D") (class "Default")
      (node (ref "CONNSIDE1") (pin "P$4") (pinfunction "4_P$4") (pintype "passive"))
      (node (ref "CONNSIDE2") (pin "P$4") (pinfunction "4_P$4") (pintype "passive"))
      (node (ref "CONNSIDE3") (pin "P$4") (pinfunction "4_P$4") (pintype "passive"))
      (node (ref "CONNSIDE4") (pin "P$4") (pinfunction "4_P$4") (pintype "passive"))
      (node (ref "CONNSIDE5") (pin "P$4") (pinfunction "4_P$4") (pintype "passive"))
      (node (ref "DRIVECONN") (pin "P$8") (pinfunction "P$8_P$8") (pintype "bidirectional"))
      (node (ref "IR_PMOS") (pin "5") (pinfunction "D_5") (pintype "passive"))
      (node (ref "IR_PMOS") (pin "6") (pinfunction "D_6") (pintype "passive"))
      (node (ref "IR_PMOS") (pin "7") (pinfunction "D_7") (pintype "passive"))
      (node (ref "IR_PMOS") (pin "8") (pinfunction "D_8") (pintype "passive"))
      (node (ref "R17") (pin "2") (pinfunction "2_2") (pintype "passive"))
    )
    (net (code "3") (name "3V6") (class "Default")
      (node (ref "C20") (pin "1") (pinfunction "1_1") (pintype "passive"))
      (node (ref "LTC3112") (pin "8") (pinfunction "VOUT_8") (pintype "bidirectional"))
      (node (ref "R3") (pin "1") (pinfunction "1_1") (pintype "passive"))
      (node (ref "R7") (pin "1") (pinfunction "1_1") (pintype "passive"))
      (node (ref "RADCONNM") (pin "P$1") (pinfunction "1_P$1") (pintype "bidirectional"))
      (node (ref "RADCONNM") (pin "P$10") (pinfunction "10_P$10") (pintype "bidirectional"))
    )
    (net (code "4") (name "5V") (class "Default")
      (node (ref "63002") (pin "P$1") (pinfunction "VOUT_P$1") (pintype "output"))
      (node (ref "63002") (pin "P$10") (pinfunction "FB_P$10") (pintype "input"))
      (node (ref "BATTCONN") (pin "P$5") (pinfunction "P$5_P$5") (pintype "bidirectional"))
      (node (ref "C15") (pin "2") (pinfunction "2_2") (pintype "passive"))
      (node (ref "CNTRLT") (pin "P$1") (pinfunction "V+_P$1") (pintype "bidirectional"))
      (node (ref "DRIVECONN") (pin "P$26") (pinfunction "P$26_P$26") (pintype "bidirectional"))
      (node (ref "T_AMP") (pin "V+") (pinfunction "V+_V+") (pintype "power_in"))
    )
    (net (code "5") (name "AMBTEMP") (class "Default")
      (node (ref "DRIVECONN") (pin "P$5") (pinfunction "P$5_P$5") (pintype "bidirectional"))
      (node (ref "T-DM") (pin "P$4") (pinfunction "B1_P$4") (pintype "bidirectional"))
    )
    (net (code "6") (name "BAL_1_ENABLE") (class "Default")
      (node (ref "UMBCONN") (pin "P$15") (pinfunction "P$15_P$15") (pintype "bidirectional"))
    )
    (net (code "7") (name "BAL_2_EN") (class "Default")
      (node (ref "UMBCONN") (pin "P$16") (pinfunction "P$16_P$16") (pintype "bidirectional"))
    )
    (net (code "8") (name "BATT1TEMP") (class "Default")
      (node (ref "BATTCONN") (pin "P$1") (pinfunction "P$1_P$1") (pintype "bidirectional"))
      (node (ref "T-DM") (pin "P$15") (pinfunction "B5_P$15") (pintype "bidirectional"))
    )
    (net (code "9") (name "BATT2TEMP") (class "Default")
      (node (ref "BATTCONN") (pin "P$2") (pinfunction "P$2_P$2") (pintype "bidirectional"))
      (node (ref "T-DM") (pin "P$14") (pinfunction "B6_P$14") (pintype "bidirectional"))
    )
    (net (code "10") (name "BATT3TEMP") (class "Default")
      (node (ref "BATTCONN") (pin "P$3") (pinfunction "P$3_P$3") (pintype "bidirectional"))
      (node (ref "T-DM") (pin "P$13") (pinfunction "B7_P$13") (pintype "bidirectional"))
    )
    (net (code "11") (name "BATT4TEMP") (class "Default")
      (node (ref "BATTCONN") (pin "P$4") (pinfunction "P$4_P$4") (pintype "bidirectional"))
      (node (ref "T-DM") (pin "P$12") (pinfunction "B8_P$12") (pintype "bidirectional"))
    )
    (net (code "12") (name "CNTRLTEMP") (class "Default")
      (node (ref "CNTRLT") (pin "P$2") (pinfunction "V-_P$2") (pintype "bidirectional"))
      (node (ref "T-DM") (pin "P$1") (pinfunction "B4_P$1") (pintype "bidirectional"))
    )
    (net (code "13") (name "DRIVE3TEMP") (class "Default")
      (node (ref "DRIVECONN") (pin "P$6") (pinfunction "P$6_P$6") (pintype "bidirectional"))
      (node (ref "T-DM") (pin "P$3") (pinfunction "B2_P$3") (pintype "bidirectional"))
    )
    (net (code "14") (name "DRIVE4TEMP") (class "Default")
      (node (ref "DRIVECONN") (pin "P$7") (pinfunction "P$7_P$7") (pintype "bidirectional"))
      (node (ref "T-DM") (pin "P$2") (pinfunction "B3_P$2") (pintype "bidirectional"))
    )
    (net (code "15") (name "DRIVE_SENSE_1") (class "Default")
      (node (ref "DRIVECONN") (pin "P$17") (pinfunction "P$17_P$17") (pintype "bidirectional"))
      (node (ref "TD-DM") (pin "P$6") (pinfunction "1B1_P$6") (pintype "bidirectional"))
    )
    (net (code "16") (name "DRIVE_SENSE_2") (class "Default")
      (node (ref "DRIVECONN") (pin "P$18") (pinfunction "P$18_P$18") (pintype "bidirectional"))
      (node (ref "TD-DM") (pin "P$5") (pinfunction "1B2_P$5") (pintype "bidirectional"))
    )
    (net (code "17") (name "DRIVE_SENSE_3") (class "Default")
      (node (ref "DRIVECONN") (pin "P$19") (pinfunction "P$19_P$19") (pintype "bidirectional"))
      (node (ref "TD-DM") (pin "P$4") (pinfunction "1B3_P$4") (pintype "bidirectional"))
    )
    (net (code "18") (name "DRIVE_SENSE_4") (class "Default")
      (node (ref "DRIVECONN") (pin "P$20") (pinfunction "P$20_P$20") (pintype "bidirectional"))
      (node (ref "TD-DM") (pin "P$3") (pinfunction "1B4_P$3") (pintype "bidirectional"))
    )
    (net (code "19") (name "GND") (class "Default")
      (node (ref "63001") (pin "P$3") (pinfunction "PGND_P$3") (pintype "input"))
      (node (ref "63001") (pin "P$9") (pinfunction "GND_P$9") (pintype "input"))
      (node (ref "63001") (pin "PAD") (pinfunction "GND_PAD") (pintype "input"))
      (node (ref "63002") (pin "P$3") (pinfunction "PGND_P$3") (pintype "input"))
      (node (ref "63002") (pin "P$9") (pinfunction "GND_P$9") (pintype "input"))
      (node (ref "63002") (pin "PAD") (pinfunction "GND_PAD") (pintype "input"))
      (node (ref "BAL_1_BUF") (pin "P$3") (pinfunction "GND_P$3") (pintype "bidirectional"))
      (node (ref "BAL_2_BUF") (pin "P$3") (pinfunction "GND_P$3") (pintype "bidirectional"))
      (node (ref "BATTCONN") (pin "P$20") (pinfunction "P$20_P$20") (pintype "bidirectional"))
      (node (ref "BATTCONN") (pin "P$21") (pinfunction "P$21_P$21") (pintype "bidirectional"))
      (node (ref "BATTCONN") (pin "P$22") (pinfunction "P$22_P$22") (pintype "bidirectional"))
      (node (ref "C1") (pin "2") (pinfunction "2_2") (pintype "passive"))
      (node (ref "C11") (pin "1") (pinfunction "1_1") (pintype "passive"))
      (node (ref "C12") (pin "2") (pinfunction "2_2") (pintype "passive"))
      (node (ref "C14") (pin "1") (pinfunction "1_1") (pintype "passive"))
      (node (ref "C15") (pin "1") (pinfunction "1_1") (pintype "passive"))
      (node (ref "C17") (pin "2") (pinfunction "2_2") (pintype "passive"))
      (node (ref "C18") (pin "2") (pinfunction "2_2") (pintype "passive"))
      (node (ref "C19") (pin "2") (pinfunction "2_2") (pintype "passive"))
      (node (ref "C2") (pin "1") (pinfunction "1_1") (pintype "passive"))
      (node (ref "C20") (pin "2") (pinfunction "2_2") (pintype "passive"))
      (node (ref "C23") (pin "1") (pinfunction "1_1") (pintype "passive"))
      (node (ref "C26") (pin "2") (pinfunction "2_2") (pintype "passive"))
      (node (ref "C27") (pin "2") (pinfunction "2_2") (pintype "passive"))
      (node (ref "C3") (pin "2") (pinfunction "2_2") (pintype "passive"))
      (node (ref "C4") (pin "1") (pinfunction "1_1") (pintype "passive"))
      (node (ref "C5") (pin "1") (pinfunction "1_1") (pintype "passive"))
      (node (ref "C6") (pin "1") (pinfunction "1_1") (pintype "passive"))
      (node (ref "C7") (pin "1") (pinfunction "1_1") (pintype "passive"))
      (node (ref "C8") (pin "1") (pinfunction "1_1") (pintype "passive"))
      (node (ref "C9") (pin "1") (pinfunction "1_1") (pintype "passive"))
      (node (ref "CH1-DM") (pin "P$8") (pinfunction "GND_P$8") (pintype "bidirectional"))
      (node (ref "CH2-DM") (pin "P$8") (pinfunction "GND_P$8") (pintype "bidirectional"))
      (node (ref "CONNSIDE1") (pin "P$5") (pinfunction "5_P$5") (pintype "passive"))
      (node (ref "CONNSIDE2") (pin "P$5") (pinfunction "5_P$5") (pintype "passive"))
      (node (ref "CONNSIDE3") (pin "P$5") (pinfunction "5_P$5") (pintype "passive"))
      (node (ref "CONNSIDE4") (pin "P$5") (pinfunction "5_P$5") (pintype "passive"))
      (node (ref "CONNSIDE5") (pin "P$5") (pinfunction "5_P$5") (pintype "passive"))
      (node (ref "DRIVECONN") (pin "P$24") (pinfunction "P$24_P$24") (pintype "bidirectional"))
      (node (ref "DRIVECONN") (pin "P$25") (pinfunction "P$25_P$25") (pintype "bidirectional"))
      (node (ref "IR_NMOS") (pin "P$1") (pinfunction "S_P$1") (pintype "passive"))
      (node (ref "IR_NMOS") (pin "P$2") (pinfunction "S_P$2") (pintype "passive"))
      (node (ref "IR_NMOS") (pin "P$3") (pinfunction "S_P$3") (pintype "passive"))
      (node (ref "LED_EN_BUF") (pin "P$3") (pinfunction "GND_P$3") (pintype "bidirectional"))
      (node (ref "LTC3112") (pin "17") (pinfunction "GND_17") (pintype "bidirectional"))
      (node (ref "MAG") (pin "11") (pinfunction "GND_11") (pintype "bidirectional"))
      (node (ref "MAG") (pin "9") (pinfunction "GND_9") (pintype "bidirectional"))
      (node (ref "MRAM") (pin "P4") (pinfunction "GND_P4") (pintype "bidirectional"))
      (node (ref "MRAM") (pin "P9") (pinfunction "GND_P9") (pintype "bidirectional"))
      (node (ref "PH-DM") (pin "P$8") (pinfunction "GND_P$8") (pintype "bidirectional"))
      (node (ref "PH_AMP_1") (pin "IN+") (pinfunction "IN+_IN+") (pintype "input"))
      (node (ref "PH_AMP_1") (pin "V-") (pinfunction "V-_V-") (pintype "power_in"))
      (node (ref "PH_AMP_2") (pin "V-") (pinfunction "V-_V-") (pintype "power_in"))
      (node (ref "PROGCONN") (pin "2") (pinfunction "2_2") (pintype "bidirectional"))
      (node (ref "PROGCONN") (pin "3") (pinfunction "3_3") (pintype "bidirectional"))
      (node (ref "PWR_ON") (pin "C") (pinfunction "C_C") (pintype "bidirectional"))
      (node (ref "R12") (pin "2") (pinfunction "2_2") (pintype "passive"))
      (node (ref "R16") (pin "1") (pinfunction "1_1") (pintype "passive"))
      (node (ref "R17") (pin "1") (pinfunction "1_1") (pintype "passive"))
      (node (ref "R33") (pin "1") (pinfunction "1_1") (pintype "passive"))
      (node (ref "R35") (pin "1") (pinfunction "1_1") (pintype "passive"))
      (node (ref "R36") (pin "1") (pinfunction "1_1") (pintype "passive"))
      (node (ref "R37") (pin "1") (pinfunction "1_1") (pintype "passive"))
      (node (ref "R40") (pin "1") (pinfunction "1_1") (pintype "passive"))
      (node (ref "R5") (pin "1") (pinfunction "1_1") (pintype "passive"))
      (node (ref "R6") (pin "1") (pinfunction "1_1") (pintype "passive"))
      (node (ref "R8") (pin "1") (pinfunction "1_1") (pintype "passive"))
      (node (ref "R9") (pin "2") (pinfunction "2_2") (pintype "passive"))
      (node (ref "RADCONNM") (pin "P$2") (pinfunction "2_P$2") (pintype "bidirectional"))
      (node (ref "RADCONNM") (pin "P$9") (pinfunction "9_P$9") (pintype "bidirectional"))
      (node (ref "RAD_SHDN_BUF") (pin "P$3") (pinfunction "GND_P$3") (pintype "bidirectional"))
      (node (ref "RET") (pin "C") (pinfunction "C_C") (pintype "bidirectional"))
      (node (ref "RX_BUF") (pin "P$3") (pinfunction "GND_P$3") (pintype "bidirectional"))
      (node (ref "SAMD21J") (pin "P$22") (pinfunction "GND_P$22") (pintype "power_in"))
      (node (ref "SAMD21J") (pin "P$33") (pinfunction "GND_P$33") (pintype "power_in"))
      (node (ref "SAMD21J") (pin "P$47") (pinfunction "GND_P$47") (pintype "power_in"))
      (node (ref "SAMD21J") (pin "P$54") (pinfunction "GND_P$54") (pintype "power_in"))
      (node (ref "SAMD21J") (pin "P$7") (pinfunction "GNDANA_P$7") (pintype "power_in"))
      (node (ref "SEND") (pin "C") (pinfunction "C_C") (pintype "bidirectional"))
      (node (ref "T-DM") (pin "P$8") (pinfunction "GND_P$8") (pintype "bidirectional"))
      (node (ref "TD-DM") (pin "P$8") (pinfunction "GND_P$8") (pintype "bidirectional"))
      (node (ref "TX_BUF") (pin "P$3") (pinfunction "GND_P$3") (pintype "bidirectional"))
      (node (ref "T_AMP") (pin "V-") (pinfunction "V-_V-") (pintype "power_in"))
    )
    (net (code "20") (name "LED1TEMP") (class "Default")
      (node (ref "DRIVECONN") (pin "P$1") (pinfunction "P$1_P$1") (pintype "bidirectional"))
      (node (ref "TD-DM") (pin "P$10") (pinfunction "2B1_P$10") (pintype "bidirectional"))
    )
    (net (code "21") (name "LED2TEMP") (class "Default")
      (node (ref "DRIVECONN") (pin "P$2") (pinfunction "P$2_P$2") (pintype "bidirectional"))
      (node (ref "TD-DM") (pin "P$11") (pinfunction "2B2_P$11") (pintype "bidirectional"))
    )
    (net (code "22") (name "LED3TEMP") (class "Default")
      (node (ref "DRIVECONN") (pin "P$3") (pinfunction "P$3_P$3") (pintype "bidirectional"))
      (node (ref "TD-DM") (pin "P$12") (pinfunction "2B3_P$12") (pintype "bidirectional"))
    )
    (net (code "23") (name "LED4TEMP") (class "Default")
      (node (ref "DRIVECONN") (pin "P$4") (pinfunction "P$4_P$4") (pintype "bidirectional"))
      (node (ref "TD-DM") (pin "P$13") (pinfunction "2B4_P$13") (pintype "bidirectional"))
    )
    (net (code "24") (name "LFE_1_MP_EN") (class "Default")
      (node (ref "BAL_1_BUF") (pin "P$4") (pinfunction "OUT_P$4") (pintype "bidirectional"))
      (node (ref "BATTCONN") (pin "P$9") (pinfunction "P$9_P$9") (pintype "bidirectional"))
    )
    (net (code "25") (name "LFE_1_MP_NCH") (class "Default")
      (node (ref "BATTCONN") (pin "P$10") (pinfunction "P$10_P$10") (pintype "bidirectional"))
      (node (ref "CH1-DM") (pin "P$2") (pinfunction "B3_P$2") (pintype "bidirectional"))
    )
    (net (code "26") (name "LFE_1_MP_NFLT") (class "Default")
      (node (ref "BATTCONN") (pin "P$11") (pinfunction "P$11_P$11") (pintype "bidirectional"))
      (node (ref "CH1-DM") (pin "P$1") (pinfunction "B4_P$1") (pintype "bidirectional"))
    )
    (net (code "27") (name "LFE_1_SENSE") (class "Default")
      (node (ref "BATTCONN") (pin "P$26") (pinfunction "P$26_P$26") (pintype "bidirectional"))
      (node (ref "CH1-DM") (pin "P$13") (pinfunction "B7_P$13") (pintype "bidirectional"))
    )
    (net (code "28") (name "LFE_1_V") (class "Default")
      (node (ref "BATTCONN") (pin "P$15") (pinfunction "P$15_P$15") (pintype "bidirectional"))
      (node (ref "CH2-DM") (pin "P$4") (pinfunction "B1_P$4") (pintype "bidirectional"))
    )
    (net (code "29") (name "LFE_2_MP_EN") (class "Default")
      (node (ref "BAL_2_BUF") (pin "P$4") (pinfunction "OUT_P$4") (pintype "bidirectional"))
      (node (ref "BATTCONN") (pin "P$12") (pinfunction "P$12_P$12") (pintype "bidirectional"))
    )
    (net (code "30") (name "LFE_2_MP_NCH") (class "Default")
      (node (ref "BATTCONN") (pin "P$13") (pinfunction "P$13_P$13") (pintype "bidirectional"))
      (node (ref "CH1-DM") (pin "P$15") (pinfunction "B5_P$15") (pintype "bidirectional"))
    )
    (net (code "31") (name "LFE_2_MP_NFLT") (class "Default")
      (node (ref "BATTCONN") (pin "P$14") (pinfunction "P$14_P$14") (pintype "bidirectional"))
      (node (ref "CH1-DM") (pin "P$14") (pinfunction "B6_P$14") (pintype "bidirectional"))
    )
    (net (code "32") (name "LFE_2_SENSE") (class "Default")
      (node (ref "BATTCONN") (pin "P$27") (pinfunction "P$27_P$27") (pintype "bidirectional"))
      (node (ref "CH1-DM") (pin "P$12") (pinfunction "B8_P$12") (pintype "bidirectional"))
    )
    (net (code "33") (name "LFE_2_V") (class "Default")
      (node (ref "BATTCONN") (pin "P$16") (pinfunction "P$16_P$16") (pintype "bidirectional"))
      (node (ref "CH2-DM") (pin "P$3") (pinfunction "B2_P$3") (pintype "bidirectional"))
    )
    (net (code "34") (name "LFE_3_V") (class "Default")
      (node (ref "BATTCONN") (pin "P$17") (pinfunction "P$17_P$17") (pintype "bidirectional"))
      (node (ref "CH2-DM") (pin "P$2") (pinfunction "B3_P$2") (pintype "bidirectional"))
    )
    (net (code "35") (name "LFE_4_V") (class "Default")
      (node (ref "BATTCONN") (pin "P$18") (pinfunction "P$18_P$18") (pintype "bidirectional"))
      (node (ref "CH2-DM") (pin "P$1") (pinfunction "B4_P$1") (pintype "bidirectional"))
    )
    (net (code "36") (name "LITH_MP_NCH") (class "Default")
      (node (ref "BATTCONN") (pin "P$7") (pinfunction "P$7_P$7") (pintype "bidirectional"))
      (node (ref "CH1-DM") (pin "P$4") (pinfunction "B1_P$4") (pintype "bidirectional"))
    )
    (net (code "37") (name "LITH_MP_NFLT") (class "Default")
      (node (ref "BATTCONN") (pin "P$8") (pinfunction "P$8_P$8") (pintype "bidirectional"))
      (node (ref "CH1-DM") (pin "P$3") (pinfunction "B2_P$3") (pintype "bidirectional"))
    )
    (net (code "38") (name "Net-(1N4148-PadCATHODE)") (class "Default")
      (node (ref "1N4148") (pin "CATHODE") (pinfunction "CATHODE_CATHODE") (pintype "bidirectional"))
      (node (ref "PH_AMP_1") (pin "OUT") (pinfunction "OUT_OUT") (pintype "output"))
      (node (ref "R32") (pin "1") (pinfunction "1_1") (pintype "passive"))
    )
    (net (code "39") (name "Net-(100T-1)") (class "Default")
      (node (ref "100T") (pin "P$1") (pinfunction "1_P$1") (pintype "bidirectional"))
      (node (ref "R16") (pin "2") (pinfunction "2_2") (pintype "passive"))
    )
    (net (code "40") (name "Net-(63001-L1)") (class "Default")
      (node (ref "63001") (pin "P$4") (pinfunction "L1_P$4") (pintype "input"))
      (node (ref "L2") (pin "1") (pinfunction "1_1") (pintype "passive"))
    )
    (net (code "41") (name "Net-(63001-L2)") (class "Default")
      (node (ref "63001") (pin "P$2") (pinfunction "L2_P$2") (pintype "input"))
      (node (ref "L2") (pin "2") (pinfunction "2_2") (pintype "passive"))
    )
    (net (code "42") (name "Net-(63002-L1)") (class "Default")
      (node (ref "63002") (pin "P$4") (pinfunction "L1_P$4") (pintype "input"))
      (node (ref "L3") (pin "1") (pinfunction "1_1") (pintype "passive"))
    )
    (net (code "43") (name "Net-(63002-L2)") (class "Default")
      (node (ref "63002") (pin "P$2") (pinfunction "L2_P$2") (pintype "input"))
      (node (ref "L3") (pin "2") (pinfunction "2_2") (pintype "passive"))
    )
    (net (code "44") (name "Net-(C21-Pad2)") (class "Default")
      (node (ref "C21") (pin "2") (pinfunction "2_2") (pintype "passive"))
      (node (ref "L4") (pin "2") (pinfunction "2_2") (pintype "passive"))
      (node (ref "LTC3112") (pin "10") (pinfunction "SW2_10") (pintype "bidirectional"))
      (node (ref "LTC3112") (pin "9") (pinfunction "SW2_9") (pintype "bidirectional"))
    )
    (net (code "45") (name "Net-(C22-Pad2)") (class "Default")
      (node (ref "C22") (pin "2") (pinfunction "2_2") (pintype "passive"))
      (node (ref "L4") (pin "1") (pinfunction "1_1") (pintype "passive"))
      (node (ref "LTC3112") (pin "12") (pinfunction "SW1_12") (pintype "bidirectional"))
      (node (ref "LTC3112") (pin "13") (pinfunction "SW1_13") (pintype "bidirectional"))
    )
    (net (code "46") (name "Net-(C29-Pad1)") (class "Default")
      (node (ref "C29") (pin "1") (pinfunction "1_1") (pintype "passive"))
      (node (ref "R10") (pin "1") (pinfunction "1_1") (pintype "passive"))
    )
    (net (code "47") (name "Net-(IR_PMOS-G)") (class "Default")
      (node (ref "IR_NMOS") (pin "P$5") (pinfunction "D_P$5") (pintype "passive"))
      (node (ref "IR_NMOS") (pin "P$6") (pinfunction "D_P$6") (pintype "passive"))
      (node (ref "IR_NMOS") (pin "P$7") (pinfunction "D_P$7") (pintype "passive"))
      (node (ref "IR_NMOS") (pin "P$8") (pinfunction "D_P$8") (pintype "passive"))
      (node (ref "IR_NMOS") (pin "P$9") (pinfunction "D_P$9") (pintype "passive"))
      (node (ref "IR_PMOS") (pin "4") (pinfunction "G_4") (pintype "passive"))
      (node (ref "R30") (pin "1") (pinfunction "1_1") (pintype "passive"))
    )
    (net (code "48") (name "Net-(LTC3112-BST1)") (class "Default")
      (node (ref "C22") (pin "1") (pinfunction "1_1") (pintype "passive"))
      (node (ref "LTC3112") (pin "14") (pinfunction "BST1_14") (pintype "bidirectional"))
    )
    (net (code "49") (name "Net-(LTC3112-BST2)") (class "Default")
      (node (ref "C21") (pin "1") (pinfunction "1_1") (pintype "passive"))
      (node (ref "LTC3112") (pin "11") (pinfunction "BST2_11") (pintype "bidirectional"))
    )
    (net (code "50") (name "Net-(LTC3112-COMP)") (class "Default")
      (node (ref "C28") (pin "1") (pinfunction "1_1") (pintype "passive"))
      (node (ref "C29") (pin "2") (pinfunction "2_2") (pintype "passive"))
      (node (ref "LTC3112") (pin "1") (pinfunction "COMP_1") (pintype "bidirectional"))
    )
    (net (code "51") (name "Net-(LTC3112-FB)") (class "Default")
      (node (ref "C28") (pin "2") (pinfunction "2_2") (pintype "passive"))
      (node (ref "LTC3112") (pin "2") (pinfunction "FB_2") (pintype "bidirectional"))
      (node (ref "R10") (pin "2") (pinfunction "2_2") (pintype "passive"))
      (node (ref "R3") (pin "2") (pinfunction "2_2") (pintype "passive"))
      (node (ref "R4") (pin "1") (pinfunction "1_1") (pintype "passive"))
    )
    (net (code "52") (name "Net-(LTC3112-OVP)") (class "Default")
      (node (ref "C26") (pin "1") (pinfunction "1_1") (pintype "passive"))
      (node (ref "LTC3112") (pin "3") (pinfunction "OVP_3") (pintype "bidirectional"))
      (node (ref "R6") (pin "2") (pinfunction "2_2") (pintype "passive"))
      (node (ref "R7") (pin "2") (pinfunction "2_2") (pintype "passive"))
    )
    (net (code "53") (name "Net-(LTC3112-VCC)") (class "Default")
      (node (ref "C23") (pin "2") (pinfunction "2_2") (pintype "passive"))
      (node (ref "LTC3112") (pin "15") (pinfunction "VCC_15") (pintype "bidirectional"))
    )
    (net (code "54") (name "Net-(MAG-C1)") (class "Default")
      (node (ref "C1") (pin "1") (pinfunction "1_1") (pintype "passive"))
      (node (ref "MAG") (pin "10") (pinfunction "C1_10") (pintype "bidirectional"))
    )
    (net (code "55") (name "Net-(MAG-SETP)") (class "Default")
      (node (ref "C10") (pin "1") (pinfunction "1_1") (pintype "passive"))
      (node (ref "MAG") (pin "8") (pinfunction "SETP_8") (pintype "bidirectional"))
    )
    (net (code "56") (name "Net-(MRAM-SO)") (class "Default")
      (node (ref "MRAM") (pin "P2") (pinfunction "SO_P2") (pintype "bidirectional"))
      (node (ref "SAMD21J") (pin "P$42") (pinfunction "PA21_P$42") (pintype "bidirectional"))
    )
    (net (code "57") (name "Net-(MRAM-~{CS})") (class "Default")
      (node (ref "MRAM") (pin "P1") (pinfunction "~{CS}_P1") (pintype "bidirectional"))
      (node (ref "R23") (pin "2") (pinfunction "2_2") (pintype "passive"))
      (node (ref "SAMD21J") (pin "P$41") (pinfunction "PA20_P$41") (pintype "bidirectional"))
    )
    (net (code "58") (name "Net-(PH_AMP_2-PadIN+)") (class "Default")
      (node (ref "PH_AMP_2") (pin "IN+") (pinfunction "IN+_IN+") (pintype "input"))
      (node (ref "R32") (pin "2") (pinfunction "2_2") (pintype "passive"))
      (node (ref "R33") (pin "2") (pinfunction "2_2") (pintype "passive"))
    )
    (net (code "59") (name "Net-(PH_AMP_2-PadIN-)") (class "Default")
      (node (ref "PH_AMP_2") (pin "IN-") (pinfunction "IN-_IN-") (pintype "input"))
      (node (ref "R34") (pin "1") (pinfunction "1_1") (pintype "passive"))
      (node (ref "R35") (pin "2") (pinfunction "2_2") (pintype "passive"))
    )
    (net (code "60") (name "Net-(R4-Pad2)") (class "Default")
      (node (ref "R4") (pin "2") (pinfunction "2_2") (pintype "passive"))
      (node (ref "R9") (pin "1") (pinfunction "1_1") (pintype "passive"))
    )
    (net (code "61") (name "Net-(R12-Pad1)") (class "Default")
      (node (ref "R12") (pin "1") (pinfunction "1_1") (pintype "passive"))
      (node (ref "R13") (pin "2") (pinfunction "2_2") (pintype "passive"))
      (node (ref "T_AMP") (pin "IN-") (pinfunction "IN-_IN-") (pintype "input"))
    )
    (net (code "62") (name "Net-(R13-Pad1)") (class "Default")
      (node (ref "R13") (pin "1") (pinfunction "1_1") (pintype "passive"))
      (node (ref "R14") (pin "2") (pinfunction "2_2") (pintype "passive"))
      (node (ref "T_AMP") (pin "OUT") (pinfunction "OUT_OUT") (pintype "output"))
    )
    (net (code "63") (name "Net-(R15-Pad1)") (class "Default")
      (node (ref "R15") (pin "1") (pinfunction "1_1") (pintype "passive"))
      (node (ref "R5") (pin "2") (pinfunction "2_2") (pintype "passive"))
      (node (ref "T_AMP") (pin "IN+") (pinfunction "IN+_IN+") (pintype "input"))
    )
    (net (code "64") (name "Net-(SAMD21J-VDDANA)") (class "Default")
      (node (ref "C2") (pin "2") (pinfunction "2_2") (pintype "passive"))
      (node (ref "C8") (pin "2") (pinfunction "2_2") (pintype "passive"))
      (node (ref "L1") (pin "2") (pinfunction "2_2") (pintype "passive"))
      (node (ref "SAMD21J") (pin "P$8") (pinfunction "VDDANA_P$8") (pintype "power_in"))
    )
    (net (code "65") (name "Net-(SAMD21J-VDDCORE)") (class "Default")
      (node (ref "C4") (pin "2") (pinfunction "2_2") (pintype "passive"))
      (node (ref "SAMD21J") (pin "P$55") (pinfunction "VDDCORE_P$55") (pintype "power_in"))
    )
    (net (code "66") (name "P29") (class "Default")
      (node (ref "RADCONNM") (pin "P$5") (pinfunction "5_P$5") (pintype "bidirectional"))
      (node (ref "RAD_SHDN_BUF") (pin "P$4") (pinfunction "OUT_P$4") (pintype "bidirectional"))
      (node (ref "UMBCONN") (pin "P$13") (pinfunction "P$13_P$13") (pintype "bidirectional"))
    )
    (net (code "67") (name "PA00") (class "Default")
      (node (ref "MAG") (pin "15") (pinfunction "DRDY_15") (pintype "bidirectional"))
      (node (ref "SAMD21J") (pin "P$1") (pinfunction "PA00_P$1") (pintype "bidirectional"))
    )
    (net (code "68") (name "PA01") (class "Default")
      (node (ref "SAMD21J") (pin "P$2") (pinfunction "PA01_P$2") (pintype "bidirectional"))
    )
    (net (code "69") (name "PA02") (class "Default")
      (node (ref "SAMD21J") (pin "P$3") (pinfunction "PA02_P$3") (pintype "bidirectional"))
    )
    (net (code "70") (name "PA03") (class "Default")
      (node (ref "SAMD21J") (pin "P$4") (pinfunction "PA03_P$4") (pintype "bidirectional"))
    )
    (net (code "71") (name "PA04") (class "Default")
      (node (ref "SAMD21J") (pin "P$13") (pinfunction "PA04_P$13") (pintype "bidirectional"))
    )
    (net (code "72") (name "PA05") (class "Default")
      (node (ref "SAMD21J") (pin "P$14") (pinfunction "PA05_P$14") (pintype "bidirectional"))
    )
    (net (code "73") (name "PA06") (class "Default")
      (node (ref "SAMD21J") (pin "P$15") (pinfunction "PA06_P$15") (pintype "bidirectional"))
    )
    (net (code "74") (name "PA07") (class "Default")
      (node (ref "SAMD21J") (pin "P$16") (pinfunction "PA07_P$16") (pintype "bidirectional"))
    )
    (net (code "75") (name "PA08") (class "Default")
      (node (ref "BAL_1_BUF") (pin "P$2") (pinfunction "IN_P$2") (pintype "bidirectional"))
      (node (ref "SAMD21J") (pin "P$17") (pinfunction "PA08_P$17") (pintype "bidirectional"))
    )
    (net (code "76") (name "PA09") (class "Default")
      (node (ref "BAL_2_BUF") (pin "P$2") (pinfunction "IN_P$2") (pintype "bidirectional"))
      (node (ref "SAMD21J") (pin "P$18") (pinfunction "PA09_P$18") (pintype "bidirectional"))
    )
    (net (code "77") (name "PA10") (class "Default")
      (node (ref "R18") (pin "1") (pinfunction "1_1") (pintype "passive"))
      (node (ref "SAMD21J") (pin "P$19") (pinfunction "PA10_P$19") (pintype "bidirectional"))
      (node (ref "TD-DM") (pin "P$1") (pinfunction "~{1OE}_P$1") (pintype "bidirectional"))
    )
    (net (code "78") (name "PA11") (class "Default")
      (node (ref "R19") (pin "1") (pinfunction "1_1") (pintype "passive"))
      (node (ref "SAMD21J") (pin "P$20") (pinfunction "PA11_P$20") (pintype "bidirectional"))
      (node (ref "TD-DM") (pin "P$15") (pinfunction "~{2OE}_P$15") (pintype "bidirectional"))
    )
    (net (code "79") (name "PA13") (class "Default")
      (node (ref "DRIVECONN") (pin "P$12") (pinfunction "P$12_P$12") (pintype "bidirectional"))
      (node (ref "SAMD21J") (pin "P$30") (pinfunction "PA13_P$30") (pintype "bidirectional"))
    )
    (net (code "80") (name "PA14") (class "Default")
      (node (ref "DRIVECONN") (pin "P$13") (pinfunction "P$13_P$13") (pintype "bidirectional"))
      (node (ref "SAMD21J") (pin "P$31") (pinfunction "PA14_P$31") (pintype "bidirectional"))
    )
    (net (code "81") (name "PA15") (class "Default")
      (node (ref "DRIVECONN") (pin "P$14") (pinfunction "P$14_P$14") (pintype "bidirectional"))
      (node (ref "SAMD21J") (pin "P$32") (pinfunction "PA15_P$32") (pintype "bidirectional"))
    )
    (net (code "82") (name "PA16") (class "Default")
      (node (ref "LED_EN_BUF") (pin "P$2") (pinfunction "IN_P$2") (pintype "bidirectional"))
      (node (ref "SAMD21J") (pin "P$35") (pinfunction "PA16_P$35") (pintype "bidirectional"))
    )
    (net (code "83") (name "PA17") (class "Default")
      (node (ref "IR_NMOS") (pin "P$4") (pinfunction "G_P$4") (pintype "passive"))
      (node (ref "R40") (pin "2") (pinfunction "2_2") (pintype "passive"))
      (node (ref "SAMD21J") (pin "P$36") (pinfunction "PA17_P$36") (pintype "bidirectional"))
      (node (ref "UMBCONN") (pin "P$6") (pinfunction "P$6_P$6") (pintype "bidirectional"))
    )
    (net (code "84") (name "PA18") (class "Default")
      (node (ref "MRAM") (pin "P5") (pinfunction "SI_P5") (pintype "bidirectional"))
      (node (ref "R28") (pin "1") (pinfunction "1_1") (pintype "passive"))
      (node (ref "SAMD21J") (pin "P$37") (pinfunction "PA18_P$37") (pintype "bidirectional"))
    )
    (net (code "85") (name "PA19") (class "Default")
      (node (ref "MRAM") (pin "P6") (pinfunction "SCK_P6") (pintype "bidirectional"))
      (node (ref "R29") (pin "1") (pinfunction "1_1") (pintype "passive"))
      (node (ref "SAMD21J") (pin "P$38") (pinfunction "PA19_P$38") (pintype "bidirectional"))
    )
    (net (code "86") (name "PA22") (class "Default")
      (node (ref "DRIVECONN") (pin "P$15") (pinfunction "P$15_P$15") (pintype "bidirectional"))
      (node (ref "SAMD21J") (pin "P$43") (pinfunction "PA22_P$43") (pintype "bidirectional"))
    )
    (net (code "87") (name "PA23") (class "Default")
      (node (ref "DRIVECONN") (pin "P$16") (pinfunction "P$16_P$16") (pintype "bidirectional"))
      (node (ref "SAMD21J") (pin "P$44") (pinfunction "PA23_P$44") (pintype "bidirectional"))
    )
    (net (code "88") (name "PA24") (class "Default")
      (node (ref "SAMD21J") (pin "P$45") (pinfunction "PA24_P$45") (pintype "bidirectional"))
      (node (ref "TX_BUF") (pin "P$2") (pinfunction "IN_P$2") (pintype "bidirectional"))
    )
    (net (code "89") (name "PA25") (class "Default")
      (node (ref "RX_BUF") (pin "P$4") (pinfunction "OUT_P$4") (pintype "bidirectional"))
      (node (ref "SAMD21J") (pin "P$46") (pinfunction "PA25_P$46") (pintype "bidirectional"))
    )
    (net (code "90") (name "PA27") (class "Default")
      (node (ref "CH1-DM") (pin "P$7") (pinfunction "~{OE}_P$7") (pintype "bidirectional"))
      (node (ref "R22") (pin "1") (pinfunction "1_1") (pintype "passive"))
      (node (ref "SAMD21J") (pin "P$51") (pinfunction "PA27_P$51") (pintype "bidirectional"))
    )
    (net (code "91") (name "PA28") (class "Default")
      (node (ref "CH2-DM") (pin "P$7") (pinfunction "~{OE}_P$7") (pintype "bidirectional"))
      (node (ref "R31") (pin "1") (pinfunction "1_1") (pintype "passive"))
      (node (ref "SAMD21J") (pin "P$53") (pinfunction "PA28_P$53") (pintype "bidirectional"))
    )
    (net (code "92") (name "PA30") (class "Default")
      (node (ref "PROGCONN") (pin "9") (pinfunction "9_9") (pintype "bidirectional"))
      (node (ref "SAMD21J") (pin "P$57") (pinfunction "PA30_P$57") (pintype "bidirectional"))
      (node (ref "UMBCONN") (pin "P$2") (pinfunction "P$2_P$2") (pintype "bidirectional"))
    )
    (net (code "93") (name "PA31") (class "Default")
      (node (ref "PROGCONN") (pin "10") (pinfunction "10_10") (pintype "bidirectional"))
      (node (ref "SAMD21J") (pin "P$58") (pinfunction "PA31_P$58") (pintype "bidirectional"))
      (node (ref "UMBCONN") (pin "P$3") (pinfunction "P$3_P$3") (pintype "bidirectional"))
    )
    (net (code "94") (name "PB00") (class "Default")
      (node (ref "C17") (pin "1") (pinfunction "1_1") (pintype "passive"))
      (node (ref "CH1-DM") (pin "P$5") (pinfunction "A_P$5") (pintype "bidirectional"))
      (node (ref "CH2-DM") (pin "P$5") (pinfunction "A_P$5") (pintype "bidirectional"))
      (node (ref "PH_AMP_2") (pin "OUT") (pinfunction "OUT_OUT") (pintype "output"))
      (node (ref "R14") (pin "1") (pinfunction "1_1") (pintype "passive"))
      (node (ref "R34") (pin "2") (pinfunction "2_2") (pintype "passive"))
      (node (ref "SAMD21J") (pin "P$61") (pinfunction "PB00_P$61") (pintype "bidirectional"))
      (node (ref "TD-DM") (pin "P$7") (pinfunction "1A_P$7") (pintype "bidirectional"))
    )
    (net (code "95") (name "PB01") (class "Default")
      (node (ref "RAD_SHDN_BUF") (pin "P$2") (pinfunction "IN_P$2") (pintype "bidirectional"))
      (node (ref "SAMD21J") (pin "P$62") (pinfunction "PB01_P$62") (pintype "bidirectional"))
    )
    (net (code "96") (name "PB02") (class "Default")
      (node (ref "R11") (pin "1") (pinfunction "1_1") (pintype "passive"))
      (node (ref "SAMD21J") (pin "P$63") (pinfunction "PB02_P$63") (pintype "bidirectional"))
      (node (ref "TX_BUF") (pin "P$1") (pinfunction "~{OE}_P$1") (pintype "bidirectional"))
    )
    (net (code "97") (name "PB03") (class "Default")
      (node (ref "R38") (pin "2") (pinfunction "2_2") (pintype "passive"))
      (node (ref "RX_BUF") (pin "P$1") (pinfunction "~{OE}_P$1") (pintype "bidirectional"))
      (node (ref "SAMD21J") (pin "P$64") (pinfunction "PB03_P$64") (pintype "bidirectional"))
    )
    (net (code "98") (name "PB04") (class "Default")
      (node (ref "SAMD21J") (pin "P$5") (pinfunction "PB04_P$5") (pintype "bidirectional"))
    )
    (net (code "99") (name "PB05") (class "Default")
      (node (ref "SAMD21J") (pin "P$6") (pinfunction "PB05_P$6") (pintype "bidirectional"))
    )
    (net (code "100") (name "PB06") (class "Default")
      (node (ref "C27") (pin "1") (pinfunction "1_1") (pintype "passive"))
      (node (ref "LTC3112") (pin "7") (pinfunction "IOUT_7") (pintype "bidirectional"))
      (node (ref "R8") (pin "2") (pinfunction "2_2") (pintype "passive"))
      (node (ref "SAMD21J") (pin "P$9") (pinfunction "PB06_P$9") (pintype "bidirectional"))
    )
    (net (code "101") (name "PB07") (class "Default")
      (node (ref "SAMD21J") (pin "P$10") (pinfunction "PB07_P$10") (pintype "bidirectional"))
    )
    (net (code "102") (name "PB08") (class "Default")
      (node (ref "SAMD21J") (pin "P$11") (pinfunction "PB08_P$11") (pintype "bidirectional"))
    )
    (net (code "103") (name "PB09") (class "Default")
      (node (ref "SAMD21J") (pin "P$12") (pinfunction "PB09_P$12") (pintype "bidirectional"))
    )
    (net (code "104") (name "PB10") (class "Default")
      (node (ref "CH1-DM") (pin "P$9") (pinfunction "S2_P$9") (pintype "bidirectional"))
      (node (ref "CH2-DM") (pin "P$9") (pinfunction "S2_P$9") (pintype "bidirectional"))
      (node (ref "PH-DM") (pin "P$9") (pinfunction "S2_P$9") (pintype "bidirectional"))
      (node (ref "SAMD21J") (pin "P$23") (pinfunction "PB10_P$23") (pintype "bidirectional"))
      (node (ref "T-DM") (pin "P$9") (pinfunction "S2_P$9") (pintype "bidirectional"))
    )
    (net (code "105") (name "PB11") (class "Default")
      (node (ref "BATTCONN") (pin "P$6") (pinfunction "P$6_P$6") (pintype "bidirectional"))
      (node (ref "SAMD21J") (pin "P$24") (pinfunction "PB11_P$24") (pintype "bidirectional"))
    )
    (net (code "106") (name "PB12") (class "Default")
      (node (ref "CONNSIDE1") (pin "P$3") (pinfunction "3_P$3") (pintype "passive"))
      (node (ref "CONNSIDE2") (pin "P$3") (pinfunction "3_P$3") (pintype "passive"))
      (node (ref "CONNSIDE3") (pin "P$3") (pinfunction "3_P$3") (pintype "passive"))
      (node (ref "CONNSIDE4") (pin "P$3") (pinfunction "3_P$3") (pintype "passive"))
      (node (ref "CONNSIDE5") (pin "P$3") (pinfunction "3_P$3") (pintype "passive"))
      (node (ref "DRIVECONN") (pin "P$10") (pinfunction "P$10_P$10") (pintype "bidirectional"))
      (node (ref "MAG") (pin "16") (pinfunction "SDA_16") (pintype "bidirectional"))
      (node (ref "R2") (pin "2") (pinfunction "2_2") (pintype "passive"))
      (node (ref "R25") (pin "1") (pinfunction "1_1") (pintype "passive"))
      (node (ref "SAMD21J") (pin "P$25") (pinfunction "PB12_P$25") (pintype "bidirectional"))
    )
    (net (code "107") (name "PB13") (class "Default")
      (node (ref "CONNSIDE1") (pin "P$2") (pinfunction "2_P$2") (pintype "passive"))
      (node (ref "CONNSIDE2") (pin "P$2") (pinfunction "2_P$2") (pintype "passive"))
      (node (ref "CONNSIDE3") (pin "P$2") (pinfunction "2_P$2") (pintype "passive"))
      (node (ref "CONNSIDE4") (pin "P$2") (pinfunction "2_P$2") (pintype "passive"))
      (node (ref "CONNSIDE5") (pin "P$2") (pinfunction "2_P$2") (pintype "passive"))
      (node (ref "DRIVECONN") (pin "P$9") (pinfunction "P$9_P$9") (pintype "bidirectional"))
      (node (ref "MAG") (pin "1") (pinfunction "SCL_1") (pintype "bidirectional"))
      (node (ref "R1") (pin "2") (pinfunction "2_2") (pintype "passive"))
      (node (ref "R24") (pin "1") (pinfunction "1_1") (pintype "passive"))
      (node (ref "SAMD21J") (pin "P$26") (pinfunction "PB13_P$26") (pintype "bidirectional"))
    )
    (net (code "108") (name "PB15") (class "Default")
      (node (ref "SAMD21J") (pin "P$28") (pinfunction "PB15_P$28") (pintype "bidirectional"))
    )
    (net (code "109") (name "PB16") (class "Default")
      (node (ref "MRAM") (pin "P3") (pinfunction "~{WP}_P3") (pintype "bidirectional"))
      (node (ref "R26") (pin "1") (pinfunction "1_1") (pintype "passive"))
      (node (ref "SAMD21J") (pin "P$39") (pinfunction "PB16_P$39") (pintype "bidirectional"))
    )
    (net (code "110") (name "PB17") (class "Default")
      (node (ref "MRAM") (pin "P7") (pinfunction "~{HOLD}_P7") (pintype "bidirectional"))
      (node (ref "R27") (pin "1") (pinfunction "1_1") (pintype "passive"))
      (node (ref "SAMD21J") (pin "P$40") (pinfunction "PB17_P$40") (pintype "bidirectional"))
    )
    (net (code "111") (name "PB22") (class "Default")
      (node (ref "CH1-DM") (pin "P$11") (pinfunction "S0_P$11") (pintype "bidirectional"))
      (node (ref "CH2-DM") (pin "P$11") (pinfunction "S0_P$11") (pintype "bidirectional"))
      (node (ref "PH-DM") (pin "P$11") (pinfunction "S0_P$11") (pintype "bidirectional"))
      (node (ref "SAMD21J") (pin "P$49") (pinfunction "PB22_P$49") (pintype "bidirectional"))
      (node (ref "T-DM") (pin "P$11") (pinfunction "S0_P$11") (pintype "bidirectional"))
      (node (ref "TD-DM") (pin "P$14") (pinfunction "S0_P$14") (pintype "bidirectional"))
    )
    (net (code "112") (name "PB23") (class "Default")
      (node (ref "CH1-DM") (pin "P$10") (pinfunction "S1_P$10") (pintype "bidirectional"))
      (node (ref "CH2-DM") (pin "P$10") (pinfunction "S1_P$10") (pintype "bidirectional"))
      (node (ref "PH-DM") (pin "P$10") (pinfunction "S1_P$10") (pintype "bidirectional"))
      (node (ref "SAMD21J") (pin "P$50") (pinfunction "PB23_P$50") (pintype "bidirectional"))
      (node (ref "T-DM") (pin "P$10") (pinfunction "S1_P$10") (pintype "bidirectional"))
      (node (ref "TD-DM") (pin "P$2") (pinfunction "S1_P$2") (pintype "bidirectional"))
    )
    (net (code "113") (name "PB30") (class "Default")
      (node (ref "R20") (pin "1") (pinfunction "1_1") (pintype "passive"))
      (node (ref "SAMD21J") (pin "P$59") (pinfunction "PB30_P$59") (pintype "bidirectional"))
      (node (ref "T-DM") (pin "P$7") (pinfunction "~{OE}_P$7") (pintype "bidirectional"))
    )
    (net (code "114") (name "PB31") (class "Default")
      (node (ref "PH-DM") (pin "P$7") (pinfunction "~{OE}_P$7") (pintype "bidirectional"))
      (node (ref "R21") (pin "1") (pinfunction "1_1") (pintype "passive"))
      (node (ref "SAMD21J") (pin "P$60") (pinfunction "PB31_P$60") (pintype "bidirectional"))
    )
    (net (code "115") (name "PD1_OUT") (class "Default")
      (node (ref "CONNSIDE1") (pin "P$1") (pinfunction "1_P$1") (pintype "passive"))
      (node (ref "PH-DM") (pin "P$4") (pinfunction "B1_P$4") (pintype "bidirectional"))
    )
    (net (code "116") (name "PD2_OUT") (class "Default")
      (node (ref "CONNSIDE2") (pin "P$1") (pinfunction "1_P$1") (pintype "passive"))
      (node (ref "PH-DM") (pin "P$3") (pinfunction "B2_P$3") (pintype "bidirectional"))
    )
    (net (code "117") (name "PD3_OUT") (class "Default")
      (node (ref "CONNSIDE3") (pin "P$1") (pinfunction "1_P$1") (pintype "passive"))
      (node (ref "PH-DM") (pin "P$2") (pinfunction "B3_P$2") (pintype "bidirectional"))
    )
    (net (code "118") (name "PD4_OUT") (class "Default")
      (node (ref "CONNSIDE4") (pin "P$1") (pinfunction "1_P$1") (pintype "passive"))
      (node (ref "PH-DM") (pin "P$1") (pinfunction "B4_P$1") (pintype "bidirectional"))
    )
    (net (code "119") (name "PD5_OUT") (class "Default")
      (node (ref "CONNSIDE5") (pin "P$1") (pinfunction "1_P$1") (pintype "passive"))
      (node (ref "PH-DM") (pin "P$15") (pinfunction "B5_P$15") (pintype "bidirectional"))
    )
    (net (code "120") (name "PD_OUT") (class "Default")
      (node (ref "DRIVECONN") (pin "P$11") (pinfunction "P$11_P$11") (pintype "bidirectional"))
      (node (ref "PH-DM") (pin "P$14") (pinfunction "B6_P$14") (pintype "bidirectional"))
    )
    (net (code "121") (name "PH_IN") (class "Default")
      (node (ref "1N4148") (pin "ANODE") (pinfunction "ANODE_ANODE") (pintype "bidirectional"))
      (node (ref "PH-DM") (pin "P$5") (pinfunction "A_P$5") (pintype "bidirectional"))
      (node (ref "PH_AMP_1") (pin "IN-") (pinfunction "IN-_IN-") (pintype "input"))
    )
    (net (code "122") (name "R2") (class "Default")
      (node (ref "RADCONNM") (pin "P$6") (pinfunction "6_P$6") (pintype "bidirectional"))
      (node (ref "SEND") (pin "A") (pinfunction "A_A") (pintype "bidirectional"))
      (node (ref "UMBCONN") (pin "P$11") (pinfunction "P$11_P$11") (pintype "bidirectional"))
    )
    (net (code "123") (name "R3") (class "Default")
      (node (ref "RADCONNM") (pin "P$7") (pinfunction "7_P$7") (pintype "bidirectional"))
      (node (ref "TX_BUF") (pin "P$4") (pinfunction "OUT_P$4") (pintype "bidirectional"))
      (node (ref "UMBCONN") (pin "P$8") (pinfunction "P$8_P$8") (pintype "bidirectional"))
    )
    (net (code "124") (name "R4") (class "Default")
      (node (ref "RADCONNM") (pin "P$8") (pinfunction "8_P$8") (pintype "bidirectional"))
      (node (ref "RET") (pin "A") (pinfunction "A_A") (pintype "bidirectional"))
      (node (ref "UMBCONN") (pin "P$12") (pinfunction "P$12_P$12") (pintype "bidirectional"))
    )
    (net (code "125") (name "R12") (class "Default")
      (node (ref "PWR_ON") (pin "A") (pinfunction "A_A") (pintype "bidirectional"))
      (node (ref "RADCONNM") (pin "P$3") (pinfunction "3_P$3") (pintype "bidirectional"))
      (node (ref "UMBCONN") (pin "P$10") (pinfunction "P$10_P$10") (pintype "bidirectional"))
    )
    (net (code "126") (name "R14") (class "Default")
      (node (ref "RADCONNM") (pin "P$4") (pinfunction "4_P$4") (pintype "bidirectional"))
      (node (ref "RX_BUF") (pin "P$2") (pinfunction "IN_P$2") (pintype "bidirectional"))
      (node (ref "UMBCONN") (pin "P$9") (pinfunction "P$9_P$9") (pintype "bidirectional"))
    )
    (net (code "127") (name "RESETN") (class "Default")
      (node (ref "PROGCONN") (pin "6") (pinfunction "6_6") (pintype "bidirectional"))
      (node (ref "SAMD21J") (pin "P$52") (pinfunction "RESETN_P$52") (pintype "input"))
      (node (ref "UMBCONN") (pin "P$1") (pinfunction "P$1_P$1") (pintype "bidirectional"))
    )
    (net (code "128") (name "SCL") (class "Default")
      (node (ref "UMBCONN") (pin "P$5") (pinfunction "P$5_P$5") (pintype "bidirectional"))
    )
    (net (code "129") (name "SDA") (class "Default")
      (node (ref "UMBCONN") (pin "P$4") (pinfunction "P$4_P$4") (pintype "bidirectional"))
    )
    (net (code "130") (name "SETC") (class "Default")
      (node (ref "C10") (pin "2") (pinfunction "2_2") (pintype "passive"))
      (node (ref "MAG") (pin "12") (pinfunction "SETC_12") (pintype "bidirectional"))
    )
    (net (code "131") (name "SHDN_N") (class "Default")
      (node (ref "BATTCONN") (pin "P$19") (pinfunction "P$19_P$19") (pintype "bidirectional"))
      (node (ref "DRIVECONN") (pin "P$27") (pinfunction "P$27_P$27") (pintype "bidirectional"))
      (node (ref "LED_EN_BUF") (pin "P$4") (pinfunction "OUT_P$4") (pintype "bidirectional"))
      (node (ref "R37") (pin "2") (pinfunction "2_2") (pintype "passive"))
      (node (ref "UMBCONN") (pin "P$7") (pinfunction "P$7_P$7") (pintype "bidirectional"))
    )
    (net (code "132") (name "TEMP_IN") (class "Default")
      (node (ref "100T") (pin "P$3") (pinfunction "3_P$3") (pintype "bidirectional"))
      (node (ref "R15") (pin "2") (pinfunction "2_2") (pintype "passive"))
      (node (ref "T-DM") (pin "P$5") (pinfunction "A_P$5") (pintype "bidirectional"))
      (node (ref "TD-DM") (pin "P$9") (pinfunction "2A_P$9") (pintype "bidirectional"))
    )
    (net (code "133") (name "UMB_ENABLE") (class "Default")
      (node (ref "BAL_1_BUF") (pin "P$1") (pinfunction "~{OE}_P$1") (pintype "bidirectional"))
      (node (ref "BAL_2_BUF") (pin "P$1") (pinfunction "~{OE}_P$1") (pintype "bidirectional"))
      (node (ref "LED_EN_BUF") (pin "P$1") (pinfunction "~{OE}_P$1") (pintype "bidirectional"))
      (node (ref "R36") (pin "2") (pinfunction "2_2") (pintype "passive"))
      (node (ref "RAD_SHDN_BUF") (pin "P$1") (pinfunction "~{OE}_P$1") (pintype "bidirectional"))
      (node (ref "UMBCONN") (pin "P$14") (pinfunction "P$14_P$14") (pintype "bidirectional"))
    )
    (net (code "134") (name "VIN") (class "Default")
      (node (ref "63001") (pin "P$5") (pinfunction "VIN_P$5") (pintype "input"))
      (node (ref "63001") (pin "P$6") (pinfunction "EN_P$6") (pintype "input"))
      (node (ref "63001") (pin "P$7") (pinfunction "PS/SYNC_P$7") (pintype "input"))
      (node (ref "63001") (pin "P$8") (pinfunction "VINA_P$8") (pintype "input"))
      (node (ref "63002") (pin "P$5") (pinfunction "VIN_P$5") (pintype "input"))
      (node (ref "63002") (pin "P$6") (pinfunction "EN_P$6") (pintype "input"))
      (node (ref "63002") (pin "P$7") (pinfunction "PS/SYNC_P$7") (pintype "input"))
      (node (ref "63002") (pin "P$8") (pinfunction "VINA_P$8") (pintype "input"))
      (node (ref "BATTCONN") (pin "P$23") (pinfunction "P$23_P$23") (pintype "bidirectional"))
      (node (ref "BATTCONN") (pin "P$24") (pinfunction "P$24_P$24") (pintype "bidirectional"))
      (node (ref "BATTCONN") (pin "P$25") (pinfunction "P$25_P$25") (pintype "bidirectional"))
      (node (ref "C12") (pin "1") (pinfunction "1_1") (pintype "passive"))
      (node (ref "C14") (pin "2") (pinfunction "2_2") (pintype "passive"))
      (node (ref "C19") (pin "1") (pinfunction "1_1") (pintype "passive"))
      (node (ref "CH2-DM") (pin "P$15") (pinfunction "B5_P$15") (pintype "bidirectional"))
      (node (ref "LTC3112") (pin "16") (pinfunction "PWM/SYNC_16") (pintype "bidirectional"))
      (node (ref "LTC3112") (pin "4") (pinfunction "VIN_4") (pintype "bidirectional"))
      (node (ref "LTC3112") (pin "5") (pinfunction "VIN_5") (pintype "bidirectional"))
      (node (ref "LTC3112") (pin "6") (pinfunction "RUN_6") (pintype "bidirectional"))
    )
    (net (code "135") (name "unconnected-(100T-2-PadP$2)") (class "Default")
      (node (ref "100T") (pin "P$2") (pinfunction "2_P$2") (pintype "bidirectional"))
    )
    (net (code "136") (name "unconnected-(CH1-DM-NC-PadP$6)") (class "Default")
      (node (ref "CH1-DM") (pin "P$6") (pinfunction "NC_P$6") (pintype "bidirectional"))
    )
    (net (code "137") (name "unconnected-(CH2-DM-B6-PadP$14)") (class "Default")
      (node (ref "CH2-DM") (pin "P$14") (pinfunction "B6_P$14") (pintype "bidirectional"))
    )
    (net (code "138") (name "unconnected-(CH2-DM-B7-PadP$13)") (class "Default")
      (node (ref "CH2-DM") (pin "P$13") (pinfunction "B7_P$13") (pintype "bidirectional"))
    )
    (net (code "139") (name "unconnected-(CH2-DM-B8-PadP$12)") (class "Default")
      (node (ref "CH2-DM") (pin "P$12") (pinfunction "B8_P$12") (pintype "bidirectional"))
    )
    (net (code "140") (name "unconnected-(CH2-DM-NC-PadP$6)") (class "Default")
      (node (ref "CH2-DM") (pin "P$6") (pinfunction "NC_P$6") (pintype "bidirectional"))
    )
    (net (code "141") (name "unconnected-(CONNSIDE1-6-PadP$6)") (class "Default")
      (node (ref "CONNSIDE1") (pin "P$6") (pinfunction "6_P$6") (pintype "passive"))
    )
    (net (code "142") (name "unconnected-(CONNSIDE2-6-PadP$6)") (class "Default")
      (node (ref "CONNSIDE2") (pin "P$6") (pinfunction "6_P$6") (pintype "passive"))
    )
    (net (code "143") (name "unconnected-(CONNSIDE3-6-PadP$6)") (class "Default")
      (node (ref "CONNSIDE3") (pin "P$6") (pinfunction "6_P$6") (pintype "passive"))
    )
    (net (code "144") (name "unconnected-(CONNSIDE4-6-PadP$6)") (class "Default")
      (node (ref "CONNSIDE4") (pin "P$6") (pinfunction "6_P$6") (pintype "passive"))
    )
    (net (code "145") (name "unconnected-(CONNSIDE5-6-PadP$6)") (class "Default")
      (node (ref "CONNSIDE5") (pin "P$6") (pinfunction "6_P$6") (pintype "passive"))
    )
    (net (code "146") (name "unconnected-(DRIVECONN-PadP$21)") (class "Default")
      (node (ref "DRIVECONN") (pin "P$21") (pinfunction "P$21_P$21") (pintype "bidirectional"))
    )
    (net (code "147") (name "unconnected-(DRIVECONN-PadP$22)") (class "Default")
      (node (ref "DRIVECONN") (pin "P$22") (pinfunction "P$22_P$22") (pintype "bidirectional"))
    )
    (net (code "148") (name "unconnected-(DRIVECONN-PadP$23)") (class "Default")
      (node (ref "DRIVECONN") (pin "P$23") (pinfunction "P$23_P$23") (pintype "bidirectional"))
    )
    (net (code "149") (name "unconnected-(MAG-NC-Pad3)") (class "Default")
      (node (ref "MAG") (pin "3") (pinfunction "NC_3") (pintype "bidirectional"))
    )
    (net (code "150") (name "unconnected-(MAG-NC-Pad5)") (class "Default")
      (node (ref "MAG") (pin "5") (pinfunction "NC_5") (pintype "bidirectional"))
    )
    (net (code "151") (name "unconnected-(MAG-NC-Pad6)") (class "Default")
      (node (ref "MAG") (pin "6") (pinfunction "NC_6") (pintype "bidirectional"))
    )
    (net (code "152") (name "unconnected-(MAG-NC-Pad7)") (class "Default")
      (node (ref "MAG") (pin "7") (pinfunction "NC_7") (pintype "bidirectional"))
    )
    (net (code "153") (name "unconnected-(MAG-NC-Pad14)") (class "Default")
      (node (ref "MAG") (pin "14") (pinfunction "NC_14") (pintype "bidirectional"))
    )
    (net (code "154") (name "unconnected-(PH-DM-B7-PadP$13)") (class "Default")
      (node (ref "PH-DM") (pin "P$13") (pinfunction "B7_P$13") (pintype "bidirectional"))
    )
    (net (code "155") (name "unconnected-(PH-DM-B8-PadP$12)") (class "Default")
      (node (ref "PH-DM") (pin "P$12") (pinfunction "B8_P$12") (pintype "bidirectional"))
    )
    (net (code "156") (name "unconnected-(PH-DM-NC-PadP$6)") (class "Default")
      (node (ref "PH-DM") (pin "P$6") (pinfunction "NC_P$6") (pintype "bidirectional"))
    )
    (net (code "157") (name "unconnected-(PROGCONN-Pad4)") (class "Default")
      (node (ref "PROGCONN") (pin "4") (pinfunction "4_4") (pintype "bidirectional"))
    )
    (net (code "158") (name "unconnected-(PROGCONN-Pad5)") (class "Default")
      (node (ref "PROGCONN") (pin "5") (pinfunction "5_5") (pintype "bidirectional"))
    )
    (net (code "159") (name "unconnected-(PROGCONN-Pad7)") (class "Default")
      (node (ref "PROGCONN") (pin "7") (pinfunction "7_7") (pintype "bidirectional"))
    )
    (net (code "160") (name "unconnected-(PROGCONN-Pad8)") (class "Default")
      (node (ref "PROGCONN") (pin "8") (pinfunction "8_8") (pintype "bidirectional"))
    )
    (net (code "161") (name "unconnected-(SAMD21J-PA12-PadP$29)") (class "Default")
      (node (ref "SAMD21J") (pin "P$29") (pinfunction "PA12_P$29") (pintype "bidirectional"))
    )
    (net (code "162") (name "unconnected-(SAMD21J-PB14-PadP$27)") (class "Default")
      (node (ref "SAMD21J") (pin "P$27") (pinfunction "PB14_P$27") (pintype "bidirectional"))
    )
    (net (code "163") (name "unconnected-(T-DM-NC-PadP$6)") (class "Default")
      (node (ref "T-DM") (pin "P$6") (pinfunction "NC_P$6") (pintype "bidirectional"))
    )
  )
)
